# switches_place.net
KiCad netlist of a schematic drawn in Altium Designer
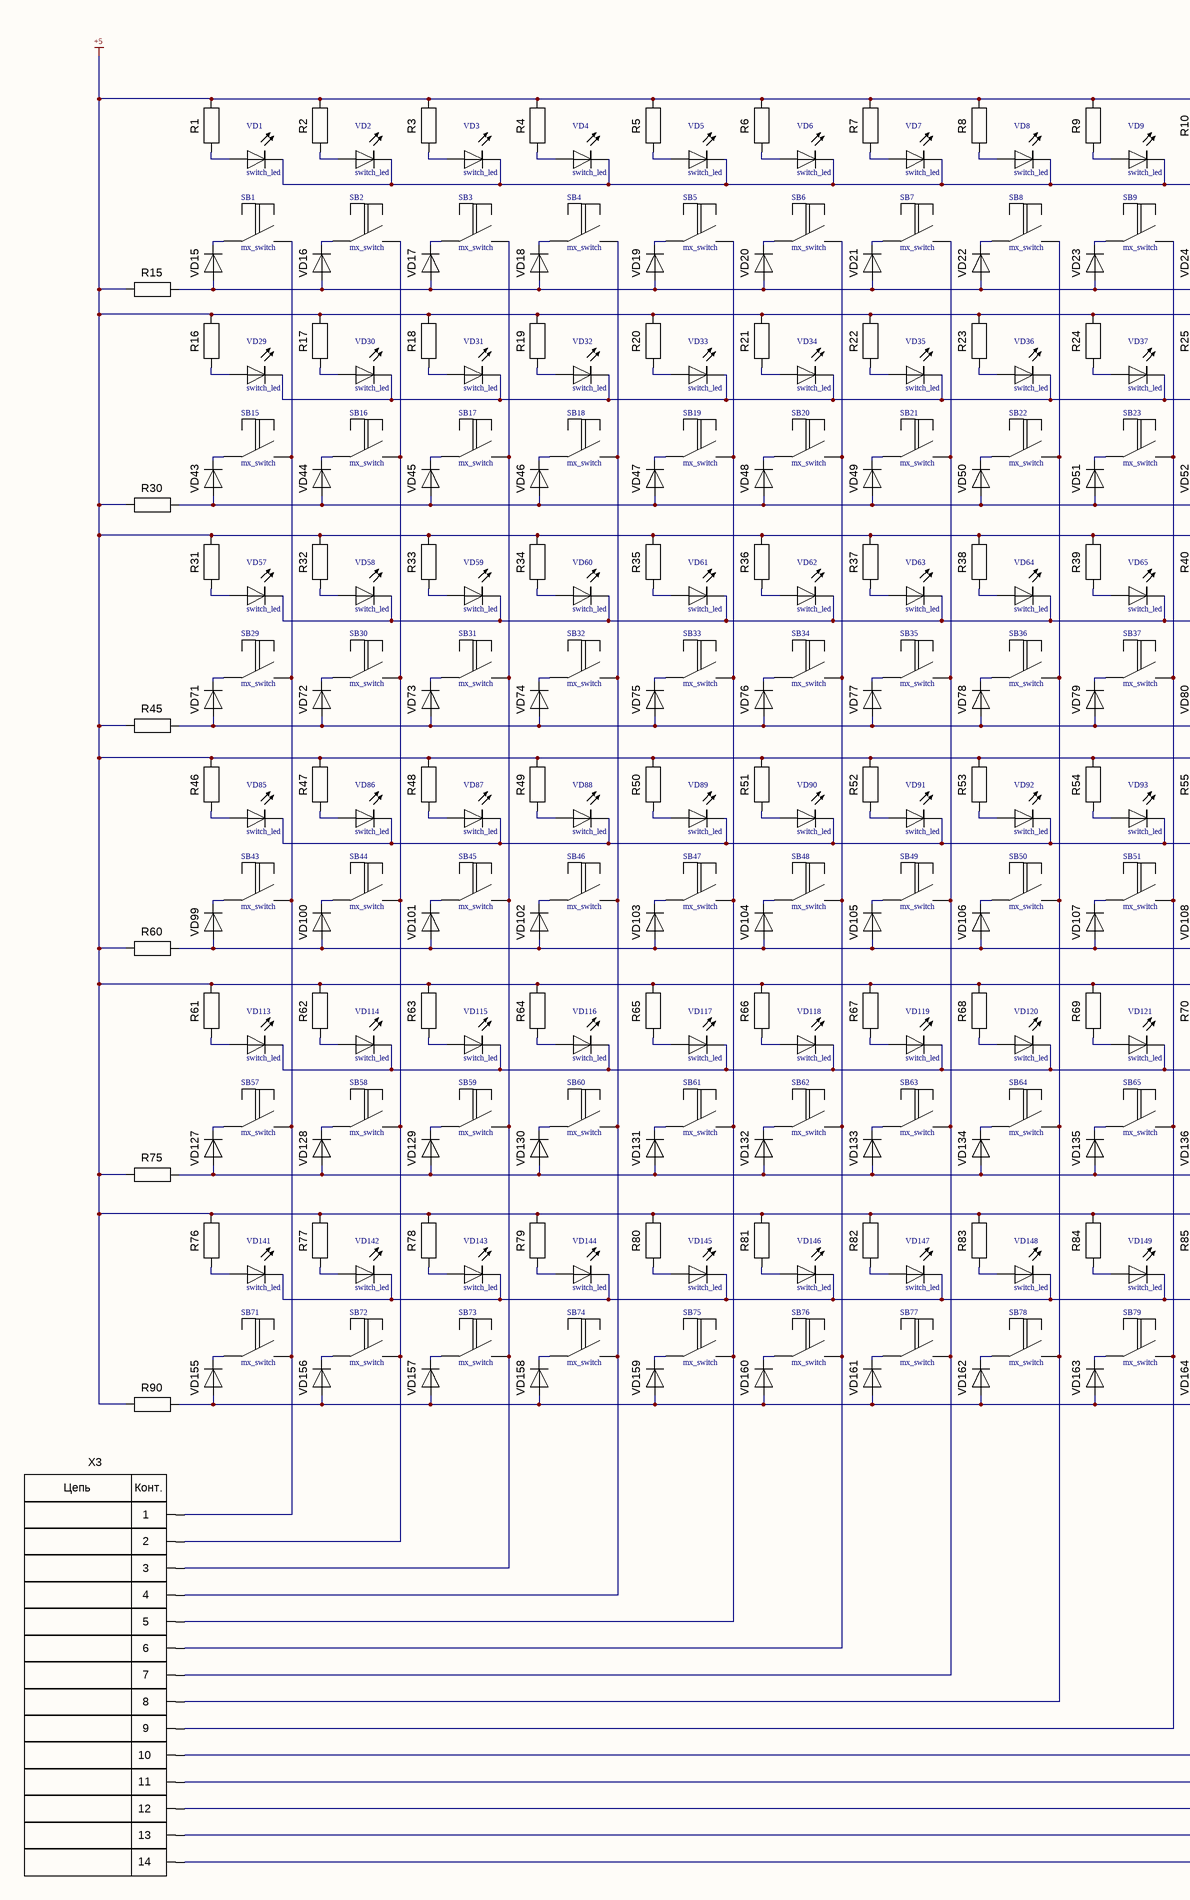
[diagram p0: switches_place.SchDoc, left]
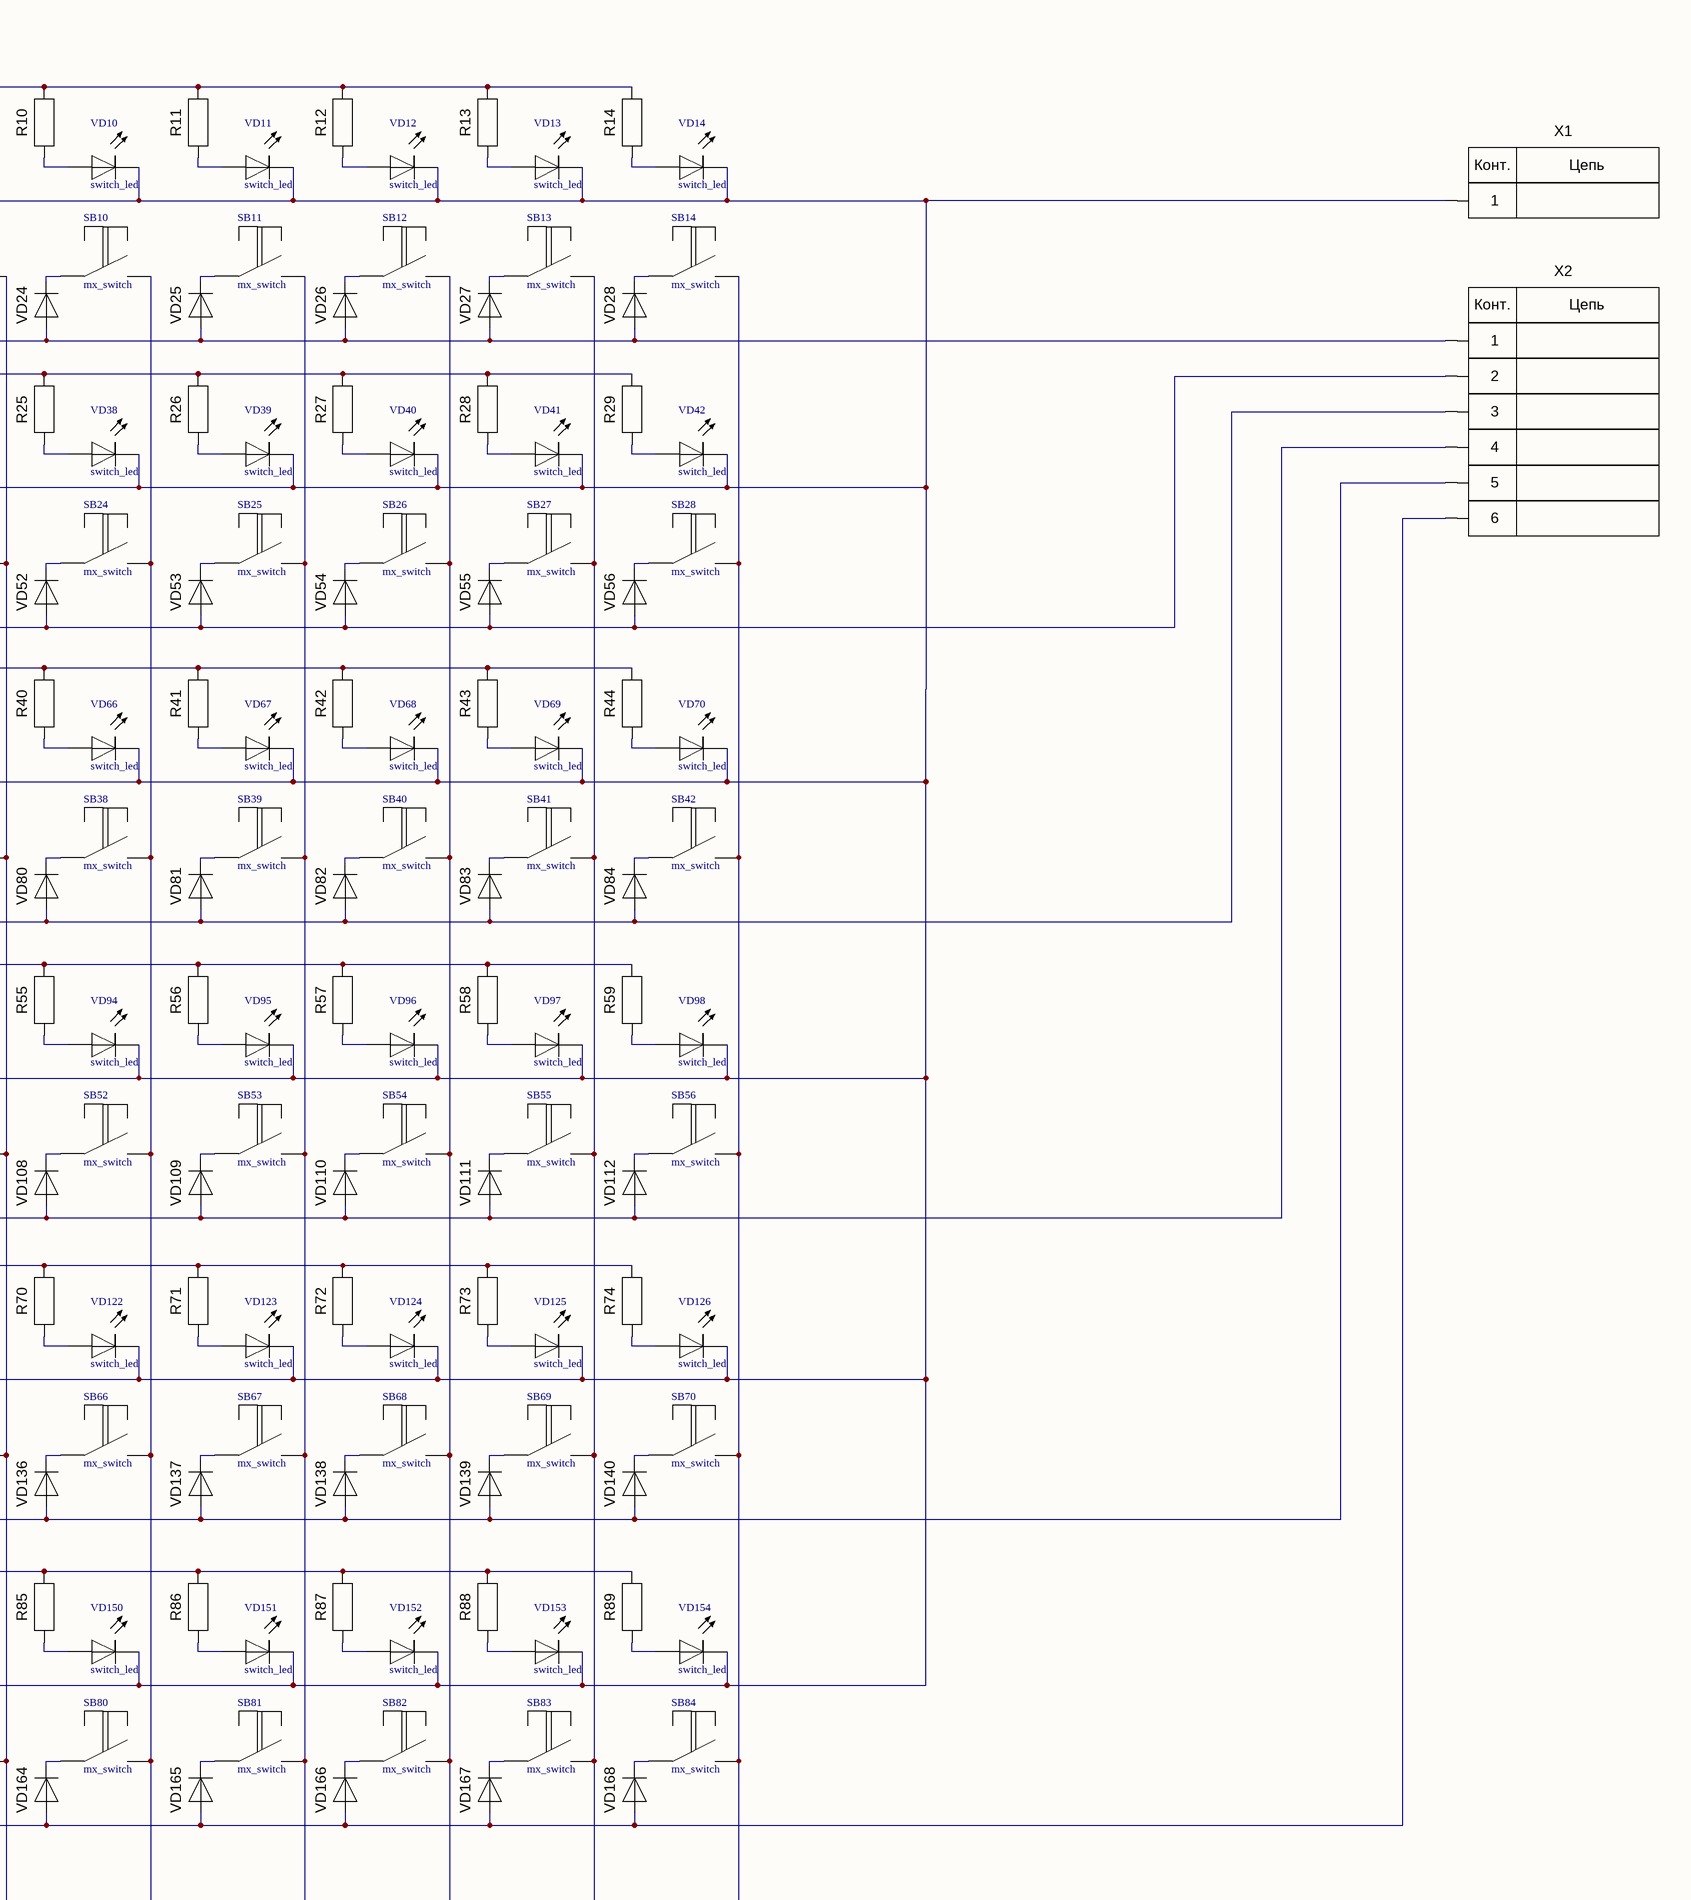
[diagram p1: switches_place.SchDoc, right]

(export (version "E")
  (design (tool "Eeschema 10.0.6"))
  (components
    (comp (ref "R1")
      (value "R")
      (footprint "R_1206")
      (fields
        (field (name "PART NUMBER") "Резистор RC1206FR-0728KL (28 кОм +-1%)")
        (field (name "TOLERANCE") "±1%")
        (field (name "POWER") "0.25 W")
      )
      (libsource (lib "GOST") (part "R"))
    )
    (comp (ref "R2")
      (value "R")
      (footprint "R_1206")
      (fields
        (field (name "PART NUMBER") "Резистор RC1206FR-0728KL (28 кОм +-1%)")
        (field (name "TOLERANCE") "±1%")
        (field (name "POWER") "0.25 W")
      )
      (libsource (lib "GOST") (part "R"))
    )
    (comp (ref "R3")
      (value "R")
      (footprint "R_1206")
      (fields
        (field (name "PART NUMBER") "Резистор RC1206FR-0728KL (28 кОм +-1%)")
        (field (name "TOLERANCE") "±1%")
        (field (name "POWER") "0.25 W")
      )
      (libsource (lib "GOST") (part "R"))
    )
    (comp (ref "R4")
      (value "R")
      (footprint "R_1206")
      (fields
        (field (name "PART NUMBER") "Резистор RC1206FR-0728KL (28 кОм +-1%)")
        (field (name "TOLERANCE") "±1%")
        (field (name "POWER") "0.25 W")
      )
      (libsource (lib "GOST") (part "R"))
    )
    (comp (ref "R5")
      (value "R")
      (footprint "R_1206")
      (fields
        (field (name "PART NUMBER") "Резистор RC1206FR-0728KL (28 кОм +-1%)")
        (field (name "TOLERANCE") "±1%")
        (field (name "POWER") "0.25 W")
      )
      (libsource (lib "GOST") (part "R"))
    )
    (comp (ref "R6")
      (value "R")
      (footprint "R_1206")
      (fields
        (field (name "PART NUMBER") "Резистор RC1206FR-0728KL (28 кОм +-1%)")
        (field (name "TOLERANCE") "±1%")
        (field (name "POWER") "0.25 W")
      )
      (libsource (lib "GOST") (part "R"))
    )
    (comp (ref "R7")
      (value "R")
      (footprint "R_1206")
      (fields
        (field (name "PART NUMBER") "Резистор RC1206FR-0728KL (28 кОм +-1%)")
        (field (name "TOLERANCE") "±1%")
        (field (name "POWER") "0.25 W")
      )
      (libsource (lib "GOST") (part "R"))
    )
    (comp (ref "R8")
      (value "R")
      (footprint "R_1206")
      (fields
        (field (name "PART NUMBER") "Резистор RC1206FR-0728KL (28 кОм +-1%)")
        (field (name "TOLERANCE") "±1%")
        (field (name "POWER") "0.25 W")
      )
      (libsource (lib "GOST") (part "R"))
    )
    (comp (ref "R9")
      (value "R")
      (footprint "R_1206")
      (fields
        (field (name "PART NUMBER") "Резистор RC1206FR-0728KL (28 кОм +-1%)")
        (field (name "TOLERANCE") "±1%")
        (field (name "POWER") "0.25 W")
      )
      (libsource (lib "GOST") (part "R"))
    )
    (comp (ref "R10")
      (value "R")
      (footprint "R_1206")
      (fields
        (field (name "PART NUMBER") "Резистор RC1206FR-0728KL (28 кОм +-1%)")
        (field (name "TOLERANCE") "±1%")
        (field (name "POWER") "0.25 W")
      )
      (libsource (lib "GOST") (part "R"))
    )
    (comp (ref "R11")
      (value "R")
      (footprint "R_1206")
      (fields
        (field (name "PART NUMBER") "Резистор RC1206FR-0728KL (28 кОм +-1%)")
        (field (name "TOLERANCE") "±1%")
        (field (name "POWER") "0.25 W")
      )
      (libsource (lib "GOST") (part "R"))
    )
    (comp (ref "R12")
      (value "R")
      (footprint "R_1206")
      (fields
        (field (name "PART NUMBER") "Резистор RC1206FR-0728KL (28 кОм +-1%)")
        (field (name "TOLERANCE") "±1%")
        (field (name "POWER") "0.25 W")
      )
      (libsource (lib "GOST") (part "R"))
    )
    (comp (ref "R13")
      (value "R")
      (footprint "R_1206")
      (fields
        (field (name "PART NUMBER") "Резистор RC1206FR-0728KL (28 кОм +-1%)")
        (field (name "TOLERANCE") "±1%")
        (field (name "POWER") "0.25 W")
      )
      (libsource (lib "GOST") (part "R"))
    )
    (comp (ref "R14")
      (value "R")
      (footprint "R_1206")
      (fields
        (field (name "PART NUMBER") "Резистор RC1206FR-0728KL (28 кОм +-1%)")
        (field (name "TOLERANCE") "±1%")
        (field (name "POWER") "0.25 W")
      )
      (libsource (lib "GOST") (part "R"))
    )
    (comp (ref "R15")
      (value "R")
      (footprint "R_1206")
      (fields
        (field (name "PART NUMBER") "Резистор RC1206FR-0716K5L (16.5 кОм +-1%)")
        (field (name "TOLERANCE") "±1%")
        (field (name "POWER") "0.25 W")
      )
      (libsource (lib "GOST") (part "R"))
    )
    (comp (ref "R16")
      (value "R")
      (footprint "R_1206")
      (fields
        (field (name "PART NUMBER") "Резистор RC1206FR-0728KL (28 кОм +-1%)")
        (field (name "TOLERANCE") "±1%")
        (field (name "POWER") "0.25 W")
      )
      (libsource (lib "GOST") (part "R"))
    )
    (comp (ref "R17")
      (value "R")
      (footprint "R_1206")
      (fields
        (field (name "PART NUMBER") "Резистор RC1206FR-0728KL (28 кОм +-1%)")
        (field (name "TOLERANCE") "±1%")
        (field (name "POWER") "0.25 W")
      )
      (libsource (lib "GOST") (part "R"))
    )
    (comp (ref "R18")
      (value "R")
      (footprint "R_1206")
      (fields
        (field (name "PART NUMBER") "Резистор RC1206FR-0728KL (28 кОм +-1%)")
        (field (name "TOLERANCE") "±1%")
        (field (name "POWER") "0.25 W")
      )
      (libsource (lib "GOST") (part "R"))
    )
    (comp (ref "R19")
      (value "R")
      (footprint "R_1206")
      (fields
        (field (name "PART NUMBER") "Резистор RC1206FR-0728KL (28 кОм +-1%)")
        (field (name "TOLERANCE") "±1%")
        (field (name "POWER") "0.25 W")
      )
      (libsource (lib "GOST") (part "R"))
    )
    (comp (ref "R20")
      (value "R")
      (footprint "R_1206")
      (fields
        (field (name "PART NUMBER") "Резистор RC1206FR-0728KL (28 кОм +-1%)")
        (field (name "TOLERANCE") "±1%")
        (field (name "POWER") "0.25 W")
      )
      (libsource (lib "GOST") (part "R"))
    )
    (comp (ref "R21")
      (value "R")
      (footprint "R_1206")
      (fields
        (field (name "PART NUMBER") "Резистор RC1206FR-0728KL (28 кОм +-1%)")
        (field (name "TOLERANCE") "±1%")
        (field (name "POWER") "0.25 W")
      )
      (libsource (lib "GOST") (part "R"))
    )
    (comp (ref "R22")
      (value "R")
      (footprint "R_1206")
      (fields
        (field (name "PART NUMBER") "Резистор RC1206FR-0728KL (28 кОм +-1%)")
        (field (name "TOLERANCE") "±1%")
        (field (name "POWER") "0.25 W")
      )
      (libsource (lib "GOST") (part "R"))
    )
    (comp (ref "R23")
      (value "R")
      (footprint "R_1206")
      (fields
        (field (name "PART NUMBER") "Резистор RC1206FR-0728KL (28 кОм +-1%)")
        (field (name "TOLERANCE") "±1%")
        (field (name "POWER") "0.25 W")
      )
      (libsource (lib "GOST") (part "R"))
    )
    (comp (ref "R24")
      (value "R")
      (footprint "R_1206")
      (fields
        (field (name "PART NUMBER") "Резистор RC1206FR-0728KL (28 кОм +-1%)")
        (field (name "TOLERANCE") "±1%")
        (field (name "POWER") "0.25 W")
      )
      (libsource (lib "GOST") (part "R"))
    )
    (comp (ref "R25")
      (value "R")
      (footprint "R_1206")
      (fields
        (field (name "PART NUMBER") "Резистор RC1206FR-0728KL (28 кОм +-1%)")
        (field (name "TOLERANCE") "±1%")
        (field (name "POWER") "0.25 W")
      )
      (libsource (lib "GOST") (part "R"))
    )
    (comp (ref "R26")
      (value "R")
      (footprint "R_1206")
      (fields
        (field (name "PART NUMBER") "Резистор RC1206FR-0728KL (28 кОм +-1%)")
        (field (name "TOLERANCE") "±1%")
        (field (name "POWER") "0.25 W")
      )
      (libsource (lib "GOST") (part "R"))
    )
    (comp (ref "R27")
      (value "R")
      (footprint "R_1206")
      (fields
        (field (name "PART NUMBER") "Резистор RC1206FR-0728KL (28 кОм +-1%)")
        (field (name "TOLERANCE") "±1%")
        (field (name "POWER") "0.25 W")
      )
      (libsource (lib "GOST") (part "R"))
    )
    (comp (ref "R28")
      (value "R")
      (footprint "R_1206")
      (fields
        (field (name "PART NUMBER") "Резистор RC1206FR-0728KL (28 кОм +-1%)")
        (field (name "TOLERANCE") "±1%")
        (field (name "POWER") "0.25 W")
      )
      (libsource (lib "GOST") (part "R"))
    )
    (comp (ref "R29")
      (value "R")
      (footprint "R_1206")
      (fields
        (field (name "PART NUMBER") "Резистор RC1206FR-0728KL (28 кОм +-1%)")
        (field (name "TOLERANCE") "±1%")
        (field (name "POWER") "0.25 W")
      )
      (libsource (lib "GOST") (part "R"))
    )
    (comp (ref "R30")
      (value "R")
      (footprint "R_1206")
      (fields
        (field (name "PART NUMBER") "Резистор RC1206FR-0716K5L (16.5 кОм +-1%)")
        (field (name "TOLERANCE") "±1%")
        (field (name "POWER") "0.25 W")
      )
      (libsource (lib "GOST") (part "R"))
    )
    (comp (ref "R31")
      (value "R")
      (footprint "R_1206")
      (fields
        (field (name "PART NUMBER") "Резистор RC1206FR-0728KL (28 кОм +-1%)")
        (field (name "TOLERANCE") "±1%")
        (field (name "POWER") "0.25 W")
      )
      (libsource (lib "GOST") (part "R"))
    )
    (comp (ref "R32")
      (value "R")
      (footprint "R_1206")
      (fields
        (field (name "PART NUMBER") "Резистор RC1206FR-0728KL (28 кОм +-1%)")
        (field (name "TOLERANCE") "±1%")
        (field (name "POWER") "0.25 W")
      )
      (libsource (lib "GOST") (part "R"))
    )
    (comp (ref "R33")
      (value "R")
      (footprint "R_1206")
      (fields
        (field (name "PART NUMBER") "Резистор RC1206FR-0728KL (28 кОм +-1%)")
        (field (name "TOLERANCE") "±1%")
        (field (name "POWER") "0.25 W")
      )
      (libsource (lib "GOST") (part "R"))
    )
    (comp (ref "R34")
      (value "R")
      (footprint "R_1206")
      (fields
        (field (name "PART NUMBER") "Резистор RC1206FR-0728KL (28 кОм +-1%)")
        (field (name "TOLERANCE") "±1%")
        (field (name "POWER") "0.25 W")
      )
      (libsource (lib "GOST") (part "R"))
    )
    (comp (ref "R35")
      (value "R")
      (footprint "R_1206")
      (fields
        (field (name "PART NUMBER") "Резистор RC1206FR-0728KL (28 кОм +-1%)")
        (field (name "TOLERANCE") "±1%")
        (field (name "POWER") "0.25 W")
      )
      (libsource (lib "GOST") (part "R"))
    )
    (comp (ref "R36")
      (value "R")
      (footprint "R_1206")
      (fields
        (field (name "PART NUMBER") "Резистор RC1206FR-0728KL (28 кОм +-1%)")
        (field (name "TOLERANCE") "±1%")
        (field (name "POWER") "0.25 W")
      )
      (libsource (lib "GOST") (part "R"))
    )
    (comp (ref "R37")
      (value "R")
      (footprint "R_1206")
      (fields
        (field (name "PART NUMBER") "Резистор RC1206FR-0728KL (28 кОм +-1%)")
        (field (name "TOLERANCE") "±1%")
        (field (name "POWER") "0.25 W")
      )
      (libsource (lib "GOST") (part "R"))
    )
    (comp (ref "R38")
      (value "R")
      (footprint "R_1206")
      (fields
        (field (name "PART NUMBER") "Резистор RC1206FR-0728KL (28 кОм +-1%)")
        (field (name "TOLERANCE") "±1%")
        (field (name "POWER") "0.25 W")
      )
      (libsource (lib "GOST") (part "R"))
    )
    (comp (ref "R39")
      (value "R")
      (footprint "R_1206")
      (fields
        (field (name "PART NUMBER") "Резистор RC1206FR-0728KL (28 кОм +-1%)")
        (field (name "TOLERANCE") "±1%")
        (field (name "POWER") "0.25 W")
      )
      (libsource (lib "GOST") (part "R"))
    )
    (comp (ref "R40")
      (value "R")
      (footprint "R_1206")
      (fields
        (field (name "PART NUMBER") "Резистор RC1206FR-0728KL (28 кОм +-1%)")
        (field (name "TOLERANCE") "±1%")
        (field (name "POWER") "0.25 W")
      )
      (libsource (lib "GOST") (part "R"))
    )
    (comp (ref "R41")
      (value "R")
      (footprint "R_1206")
      (fields
        (field (name "PART NUMBER") "Резистор RC1206FR-0728KL (28 кОм +-1%)")
        (field (name "TOLERANCE") "±1%")
        (field (name "POWER") "0.25 W")
      )
      (libsource (lib "GOST") (part "R"))
    )
    (comp (ref "R42")
      (value "R")
      (footprint "R_1206")
      (fields
        (field (name "PART NUMBER") "Резистор RC1206FR-0728KL (28 кОм +-1%)")
        (field (name "TOLERANCE") "±1%")
        (field (name "POWER") "0.25 W")
      )
      (libsource (lib "GOST") (part "R"))
    )
    (comp (ref "R43")
      (value "R")
      (footprint "R_1206")
      (fields
        (field (name "PART NUMBER") "Резистор RC1206FR-0728KL (28 кОм +-1%)")
        (field (name "TOLERANCE") "±1%")
        (field (name "POWER") "0.25 W")
      )
      (libsource (lib "GOST") (part "R"))
    )
    (comp (ref "R44")
      (value "R")
      (footprint "R_1206")
      (fields
        (field (name "PART NUMBER") "Резистор RC1206FR-0728KL (28 кОм +-1%)")
        (field (name "TOLERANCE") "±1%")
        (field (name "POWER") "0.25 W")
      )
      (libsource (lib "GOST") (part "R"))
    )
    (comp (ref "R45")
      (value "R")
      (footprint "R_1206")
      (fields
        (field (name "PART NUMBER") "Резистор RC1206FR-0716K5L (16.5 кОм +-1%)")
        (field (name "TOLERANCE") "±1%")
        (field (name "POWER") "0.25 W")
      )
      (libsource (lib "GOST") (part "R"))
    )
    (comp (ref "R46")
      (value "R")
      (footprint "R_1206")
      (fields
        (field (name "PART NUMBER") "Резистор RC1206FR-0728KL (28 кОм +-1%)")
        (field (name "TOLERANCE") "±1%")
        (field (name "POWER") "0.25 W")
      )
      (libsource (lib "GOST") (part "R"))
    )
    (comp (ref "R47")
      (value "R")
      (footprint "R_1206")
      (fields
        (field (name "PART NUMBER") "Резистор RC1206FR-0728KL (28 кОм +-1%)")
        (field (name "TOLERANCE") "±1%")
        (field (name "POWER") "0.25 W")
      )
      (libsource (lib "GOST") (part "R"))
    )
    (comp (ref "R48")
      (value "R")
      (footprint "R_1206")
      (fields
        (field (name "PART NUMBER") "Резистор RC1206FR-0728KL (28 кОм +-1%)")
        (field (name "TOLERANCE") "±1%")
        (field (name "POWER") "0.25 W")
      )
      (libsource (lib "GOST") (part "R"))
    )
    (comp (ref "R49")
      (value "R")
      (footprint "R_1206")
      (fields
        (field (name "PART NUMBER") "Резистор RC1206FR-0728KL (28 кОм +-1%)")
        (field (name "TOLERANCE") "±1%")
        (field (name "POWER") "0.25 W")
      )
      (libsource (lib "GOST") (part "R"))
    )
    (comp (ref "R50")
      (value "R")
      (footprint "R_1206")
      (fields
        (field (name "PART NUMBER") "Резистор RC1206FR-0728KL (28 кОм +-1%)")
        (field (name "TOLERANCE") "±1%")
        (field (name "POWER") "0.25 W")
      )
      (libsource (lib "GOST") (part "R"))
    )
    (comp (ref "R51")
      (value "R")
      (footprint "R_1206")
      (fields
        (field (name "PART NUMBER") "Резистор RC1206FR-0728KL (28 кОм +-1%)")
        (field (name "TOLERANCE") "±1%")
        (field (name "POWER") "0.25 W")
      )
      (libsource (lib "GOST") (part "R"))
    )
    (comp (ref "R52")
      (value "R")
      (footprint "R_1206")
      (fields
        (field (name "PART NUMBER") "Резистор RC1206FR-0728KL (28 кОм +-1%)")
        (field (name "TOLERANCE") "±1%")
        (field (name "POWER") "0.25 W")
      )
      (libsource (lib "GOST") (part "R"))
    )
    (comp (ref "R53")
      (value "R")
      (footprint "R_1206")
      (fields
        (field (name "PART NUMBER") "Резистор RC1206FR-0728KL (28 кОм +-1%)")
        (field (name "TOLERANCE") "±1%")
        (field (name "POWER") "0.25 W")
      )
      (libsource (lib "GOST") (part "R"))
    )
    (comp (ref "R54")
      (value "R")
      (footprint "R_1206")
      (fields
        (field (name "PART NUMBER") "Резистор RC1206FR-0728KL (28 кОм +-1%)")
        (field (name "TOLERANCE") "±1%")
        (field (name "POWER") "0.25 W")
      )
      (libsource (lib "GOST") (part "R"))
    )
    (comp (ref "R55")
      (value "R")
      (footprint "R_1206")
      (fields
        (field (name "PART NUMBER") "Резистор RC1206FR-0728KL (28 кОм +-1%)")
        (field (name "TOLERANCE") "±1%")
        (field (name "POWER") "0.25 W")
      )
      (libsource (lib "GOST") (part "R"))
    )
    (comp (ref "R56")
      (value "R")
      (footprint "R_1206")
      (fields
        (field (name "PART NUMBER") "Резистор RC1206FR-0728KL (28 кОм +-1%)")
        (field (name "TOLERANCE") "±1%")
        (field (name "POWER") "0.25 W")
      )
      (libsource (lib "GOST") (part "R"))
    )
    (comp (ref "R57")
      (value "R")
      (footprint "R_1206")
      (fields
        (field (name "PART NUMBER") "Резистор RC1206FR-0728KL (28 кОм +-1%)")
        (field (name "TOLERANCE") "±1%")
        (field (name "POWER") "0.25 W")
      )
      (libsource (lib "GOST") (part "R"))
    )
    (comp (ref "R58")
      (value "R")
      (footprint "R_1206")
      (fields
        (field (name "PART NUMBER") "Резистор RC1206FR-0728KL (28 кОм +-1%)")
        (field (name "TOLERANCE") "±1%")
        (field (name "POWER") "0.25 W")
      )
      (libsource (lib "GOST") (part "R"))
    )
    (comp (ref "R59")
      (value "R")
      (footprint "R_1206")
      (fields
        (field (name "PART NUMBER") "Резистор RC1206FR-0728KL (28 кОм +-1%)")
        (field (name "TOLERANCE") "±1%")
        (field (name "POWER") "0.25 W")
      )
      (libsource (lib "GOST") (part "R"))
    )
    (comp (ref "R60")
      (value "R")
      (footprint "R_1206")
      (fields
        (field (name "PART NUMBER") "Резистор RC1206FR-0716K5L (16.5 кОм +-1%)")
        (field (name "TOLERANCE") "±1%")
        (field (name "POWER") "0.25 W")
      )
      (libsource (lib "GOST") (part "R"))
    )
    (comp (ref "R61")
      (value "R")
      (footprint "R_1206")
      (fields
        (field (name "PART NUMBER") "Резистор RC1206FR-0728KL (28 кОм +-1%)")
        (field (name "TOLERANCE") "±1%")
        (field (name "POWER") "0.25 W")
      )
      (libsource (lib "GOST") (part "R"))
    )
    (comp (ref "R62")
      (value "R")
      (footprint "R_1206")
      (fields
        (field (name "PART NUMBER") "Резистор RC1206FR-0728KL (28 кОм +-1%)")
        (field (name "TOLERANCE") "±1%")
        (field (name "POWER") "0.25 W")
      )
      (libsource (lib "GOST") (part "R"))
    )
    (comp (ref "R63")
      (value "R")
      (footprint "R_1206")
      (fields
        (field (name "PART NUMBER") "Резистор RC1206FR-0728KL (28 кОм +-1%)")
        (field (name "TOLERANCE") "±1%")
        (field (name "POWER") "0.25 W")
      )
      (libsource (lib "GOST") (part "R"))
    )
    (comp (ref "R64")
      (value "R")
      (footprint "R_1206")
      (fields
        (field (name "PART NUMBER") "Резистор RC1206FR-0728KL (28 кОм +-1%)")
        (field (name "TOLERANCE") "±1%")
        (field (name "POWER") "0.25 W")
      )
      (libsource (lib "GOST") (part "R"))
    )
    (comp (ref "R65")
      (value "R")
      (footprint "R_1206")
      (fields
        (field (name "PART NUMBER") "Резистор RC1206FR-0728KL (28 кОм +-1%)")
        (field (name "TOLERANCE") "±1%")
        (field (name "POWER") "0.25 W")
      )
      (libsource (lib "GOST") (part "R"))
    )
    (comp (ref "R66")
      (value "R")
      (footprint "R_1206")
      (fields
        (field (name "PART NUMBER") "Резистор RC1206FR-0728KL (28 кОм +-1%)")
        (field (name "TOLERANCE") "±1%")
        (field (name "POWER") "0.25 W")
      )
      (libsource (lib "GOST") (part "R"))
    )
    (comp (ref "R67")
      (value "R")
      (footprint "R_1206")
      (fields
        (field (name "PART NUMBER") "Резистор RC1206FR-0728KL (28 кОм +-1%)")
        (field (name "TOLERANCE") "±1%")
        (field (name "POWER") "0.25 W")
      )
      (libsource (lib "GOST") (part "R"))
    )
    (comp (ref "R68")
      (value "R")
      (footprint "R_1206")
      (fields
        (field (name "PART NUMBER") "Резистор RC1206FR-0728KL (28 кОм +-1%)")
        (field (name "TOLERANCE") "±1%")
        (field (name "POWER") "0.25 W")
      )
      (libsource (lib "GOST") (part "R"))
    )
    (comp (ref "R69")
      (value "R")
      (footprint "R_1206")
      (fields
        (field (name "PART NUMBER") "Резистор RC1206FR-0728KL (28 кОм +-1%)")
        (field (name "TOLERANCE") "±1%")
        (field (name "POWER") "0.25 W")
      )
      (libsource (lib "GOST") (part "R"))
    )
    (comp (ref "R70")
      (value "R")
      (footprint "R_1206")
      (fields
        (field (name "PART NUMBER") "Резистор RC1206FR-0728KL (28 кОм +-1%)")
        (field (name "TOLERANCE") "±1%")
        (field (name "POWER") "0.25 W")
      )
      (libsource (lib "GOST") (part "R"))
    )
    (comp (ref "R71")
      (value "R")
      (footprint "R_1206")
      (fields
        (field (name "PART NUMBER") "Резистор RC1206FR-0728KL (28 кОм +-1%)")
        (field (name "TOLERANCE") "±1%")
        (field (name "POWER") "0.25 W")
      )
      (libsource (lib "GOST") (part "R"))
    )
    (comp (ref "R72")
      (value "R")
      (footprint "R_1206")
      (fields
        (field (name "PART NUMBER") "Резистор RC1206FR-0728KL (28 кОм +-1%)")
        (field (name "TOLERANCE") "±1%")
        (field (name "POWER") "0.25 W")
      )
      (libsource (lib "GOST") (part "R"))
    )
    (comp (ref "R73")
      (value "R")
      (footprint "R_1206")
      (fields
        (field (name "PART NUMBER") "Резистор RC1206FR-0728KL (28 кОм +-1%)")
        (field (name "TOLERANCE") "±1%")
        (field (name "POWER") "0.25 W")
      )
      (libsource (lib "GOST") (part "R"))
    )
    (comp (ref "R74")
      (value "R")
      (footprint "R_1206")
      (fields
        (field (name "PART NUMBER") "Резистор RC1206FR-0728KL (28 кОм +-1%)")
        (field (name "TOLERANCE") "±1%")
        (field (name "POWER") "0.25 W")
      )
      (libsource (lib "GOST") (part "R"))
    )
    (comp (ref "R75")
      (value "R")
      (footprint "R_1206")
      (fields
        (field (name "PART NUMBER") "Резистор RC1206FR-0716K5L (16.5 кОм +-1%)")
        (field (name "TOLERANCE") "±1%")
        (field (name "POWER") "0.25 W")
      )
      (libsource (lib "GOST") (part "R"))
    )
    (comp (ref "R76")
      (value "R")
      (footprint "R_1206")
      (fields
        (field (name "PART NUMBER") "Резистор RC1206FR-0728KL (28 кОм +-1%)")
        (field (name "TOLERANCE") "±1%")
        (field (name "POWER") "0.25 W")
      )
      (libsource (lib "GOST") (part "R"))
    )
    (comp (ref "R77")
      (value "R")
      (footprint "R_1206")
      (fields
        (field (name "PART NUMBER") "Резистор RC1206FR-0728KL (28 кОм +-1%)")
        (field (name "TOLERANCE") "±1%")
        (field (name "POWER") "0.25 W")
      )
      (libsource (lib "GOST") (part "R"))
    )
    (comp (ref "R78")
      (value "R")
      (footprint "R_1206")
      (fields
        (field (name "PART NUMBER") "Резистор RC1206FR-0728KL (28 кОм +-1%)")
        (field (name "TOLERANCE") "±1%")
        (field (name "POWER") "0.25 W")
      )
      (libsource (lib "GOST") (part "R"))
    )
    (comp (ref "R79")
      (value "R")
      (footprint "R_1206")
      (fields
        (field (name "PART NUMBER") "Резистор RC1206FR-0728KL (28 кОм +-1%)")
        (field (name "TOLERANCE") "±1%")
        (field (name "POWER") "0.25 W")
      )
      (libsource (lib "GOST") (part "R"))
    )
    (comp (ref "R80")
      (value "R")
      (footprint "R_1206")
      (fields
        (field (name "PART NUMBER") "Резистор RC1206FR-0728KL (28 кОм +-1%)")
        (field (name "TOLERANCE") "±1%")
        (field (name "POWER") "0.25 W")
      )
      (libsource (lib "GOST") (part "R"))
    )
    (comp (ref "R81")
      (value "R")
      (footprint "R_1206")
      (fields
        (field (name "PART NUMBER") "Резистор RC1206FR-0728KL (28 кОм +-1%)")
        (field (name "TOLERANCE") "±1%")
        (field (name "POWER") "0.25 W")
      )
      (libsource (lib "GOST") (part "R"))
    )
    (comp (ref "R82")
      (value "R")
      (footprint "R_1206")
      (fields
        (field (name "PART NUMBER") "Резистор RC1206FR-0728KL (28 кОм +-1%)")
        (field (name "TOLERANCE") "±1%")
        (field (name "POWER") "0.25 W")
      )
      (libsource (lib "GOST") (part "R"))
    )
    (comp (ref "R83")
      (value "R")
      (footprint "R_1206")
      (fields
        (field (name "PART NUMBER") "Резистор RC1206FR-0728KL (28 кОм +-1%)")
        (field (name "TOLERANCE") "±1%")
        (field (name "POWER") "0.25 W")
      )
      (libsource (lib "GOST") (part "R"))
    )
    (comp (ref "R84")
      (value "R")
      (footprint "R_1206")
      (fields
        (field (name "PART NUMBER") "Резистор RC1206FR-0728KL (28 кОм +-1%)")
        (field (name "TOLERANCE") "±1%")
        (field (name "POWER") "0.25 W")
      )
      (libsource (lib "GOST") (part "R"))
    )
    (comp (ref "R85")
      (value "R")
      (footprint "R_1206")
      (fields
        (field (name "PART NUMBER") "Резистор RC1206FR-0728KL (28 кОм +-1%)")
        (field (name "TOLERANCE") "±1%")
        (field (name "POWER") "0.25 W")
      )
      (libsource (lib "GOST") (part "R"))
    )
    (comp (ref "R86")
      (value "R")
      (footprint "R_1206")
      (fields
        (field (name "PART NUMBER") "Резистор RC1206FR-0728KL (28 кОм +-1%)")
        (field (name "TOLERANCE") "±1%")
        (field (name "POWER") "0.25 W")
      )
      (libsource (lib "GOST") (part "R"))
    )
    (comp (ref "R87")
      (value "R")
      (footprint "R_1206")
      (fields
        (field (name "PART NUMBER") "Резистор RC1206FR-0728KL (28 кОм +-1%)")
        (field (name "TOLERANCE") "±1%")
        (field (name "POWER") "0.25 W")
      )
      (libsource (lib "GOST") (part "R"))
    )
    (comp (ref "R88")
      (value "R")
      (footprint "R_1206")
      (fields
        (field (name "PART NUMBER") "Резистор RC1206FR-0728KL (28 кОм +-1%)")
        (field (name "TOLERANCE") "±1%")
        (field (name "POWER") "0.25 W")
      )
      (libsource (lib "GOST") (part "R"))
    )
    (comp (ref "R89")
      (value "R")
      (footprint "R_1206")
      (fields
        (field (name "PART NUMBER") "Резистор RC1206FR-0728KL (28 кОм +-1%)")
        (field (name "TOLERANCE") "±1%")
        (field (name "POWER") "0.25 W")
      )
      (libsource (lib "GOST") (part "R"))
    )
    (comp (ref "R90")
      (value "R")
      (footprint "R_1206")
      (fields
        (field (name "PART NUMBER") "Резистор RC1206FR-0716K5L (16.5 кОм +-1%)")
        (field (name "TOLERANCE") "±1%")
        (field (name "POWER") "0.25 W")
      )
      (libsource (lib "GOST") (part "R"))
    )
    (comp (ref "SB1")
      (value "mx_switch")
      (footprint "cherry_mx_5pin_led")
      (libsource (lib "cherry_mx_switch") (part "mx_switch"))
    )
    (comp (ref "SB2")
      (value "mx_switch")
      (footprint "cherry_mx_5pin_led")
      (libsource (lib "cherry_mx_switch") (part "mx_switch"))
    )
    (comp (ref "SB3")
      (value "mx_switch")
      (footprint "cherry_mx_5pin_led")
      (libsource (lib "cherry_mx_switch") (part "mx_switch"))
    )
    (comp (ref "SB4")
      (value "mx_switch")
      (footprint "cherry_mx_5pin_led")
      (libsource (lib "cherry_mx_switch") (part "mx_switch"))
    )
    (comp (ref "SB5")
      (value "mx_switch")
      (footprint "cherry_mx_5pin_led")
      (libsource (lib "") (part "mx_switch_1"))
    )
    (comp (ref "SB6")
      (value "mx_switch")
      (footprint "cherry_mx_5pin_led")
      (libsource (lib "cherry_mx_switch") (part "mx_switch"))
    )
    (comp (ref "SB7")
      (value "mx_switch")
      (footprint "cherry_mx_5pin_led")
      (libsource (lib "cherry_mx_switch") (part "mx_switch"))
    )
    (comp (ref "SB8")
      (value "mx_switch")
      (footprint "cherry_mx_5pin_led")
      (libsource (lib "cherry_mx_switch") (part "mx_switch"))
    )
    (comp (ref "SB9")
      (value "mx_switch")
      (footprint "cherry_mx_5pin_led")
      (libsource (lib "cherry_mx_switch") (part "mx_switch"))
    )
    (comp (ref "SB10")
      (value "mx_switch")
      (footprint "cherry_mx_5pin_led")
      (libsource (lib "cherry_mx_switch") (part "mx_switch"))
    )
    (comp (ref "SB11")
      (value "mx_switch")
      (footprint "cherry_mx_5pin_led")
      (libsource (lib "cherry_mx_switch") (part "mx_switch"))
    )
    (comp (ref "SB12")
      (value "mx_switch")
      (footprint "cherry_mx_5pin_led")
      (libsource (lib "cherry_mx_switch") (part "mx_switch"))
    )
    (comp (ref "SB13")
      (value "mx_switch")
      (footprint "cherry_mx_5pin_led")
      (libsource (lib "cherry_mx_switch") (part "mx_switch"))
    )
    (comp (ref "SB14")
      (value "mx_switch")
      (footprint "cherry_mx_5pin_led")
      (libsource (lib "cherry_mx_switch") (part "mx_switch"))
    )
    (comp (ref "SB15")
      (value "mx_switch")
      (footprint "cherry_mx_5pin_led")
      (libsource (lib "cherry_mx_switch") (part "mx_switch"))
    )
    (comp (ref "SB16")
      (value "mx_switch")
      (footprint "cherry_mx_5pin_led")
      (libsource (lib "cherry_mx_switch") (part "mx_switch"))
    )
    (comp (ref "SB17")
      (value "mx_switch")
      (footprint "cherry_mx_5pin_led")
      (libsource (lib "cherry_mx_switch") (part "mx_switch"))
    )
    (comp (ref "SB18")
      (value "mx_switch")
      (footprint "cherry_mx_5pin_led")
      (libsource (lib "cherry_mx_switch") (part "mx_switch"))
    )
    (comp (ref "SB19")
      (value "mx_switch")
      (footprint "cherry_mx_5pin_led")
      (libsource (lib "") (part "mx_switch_1"))
    )
    (comp (ref "SB20")
      (value "mx_switch")
      (footprint "cherry_mx_5pin_led")
      (libsource (lib "cherry_mx_switch") (part "mx_switch"))
    )
    (comp (ref "SB21")
      (value "mx_switch")
      (footprint "cherry_mx_5pin_led")
      (libsource (lib "cherry_mx_switch") (part "mx_switch"))
    )
    (comp (ref "SB22")
      (value "mx_switch")
      (footprint "cherry_mx_5pin_led")
      (libsource (lib "cherry_mx_switch") (part "mx_switch"))
    )
    (comp (ref "SB23")
      (value "mx_switch")
      (footprint "cherry_mx_5pin_led")
      (libsource (lib "cherry_mx_switch") (part "mx_switch"))
    )
    (comp (ref "SB24")
      (value "mx_switch")
      (footprint "cherry_mx_5pin_led")
      (libsource (lib "cherry_mx_switch") (part "mx_switch"))
    )
    (comp (ref "SB25")
      (value "mx_switch")
      (footprint "cherry_mx_5pin_led")
      (libsource (lib "cherry_mx_switch") (part "mx_switch"))
    )
    (comp (ref "SB26")
      (value "mx_switch")
      (footprint "cherry_mx_5pin_led")
      (libsource (lib "cherry_mx_switch") (part "mx_switch"))
    )
    (comp (ref "SB27")
      (value "mx_switch")
      (footprint "cherry_mx_5pin_led")
      (libsource (lib "cherry_mx_switch") (part "mx_switch"))
    )
    (comp (ref "SB28")
      (value "mx_switch")
      (footprint "cherry_mx_5pin_led")
      (libsource (lib "cherry_mx_switch") (part "mx_switch"))
    )
    (comp (ref "SB29")
      (value "mx_switch")
      (footprint "cherry_mx_5pin_led")
      (libsource (lib "cherry_mx_switch") (part "mx_switch"))
    )
    (comp (ref "SB30")
      (value "mx_switch")
      (footprint "cherry_mx_5pin_led")
      (libsource (lib "cherry_mx_switch") (part "mx_switch"))
    )
    (comp (ref "SB31")
      (value "mx_switch")
      (footprint "cherry_mx_5pin_led")
      (libsource (lib "cherry_mx_switch") (part "mx_switch"))
    )
    (comp (ref "SB32")
      (value "mx_switch")
      (footprint "cherry_mx_5pin_led")
      (libsource (lib "cherry_mx_switch") (part "mx_switch"))
    )
    (comp (ref "SB33")
      (value "mx_switch")
      (footprint "cherry_mx_5pin_led")
      (libsource (lib "") (part "mx_switch_1"))
    )
    (comp (ref "SB34")
      (value "mx_switch")
      (footprint "cherry_mx_5pin_led")
      (libsource (lib "cherry_mx_switch") (part "mx_switch"))
    )
    (comp (ref "SB35")
      (value "mx_switch")
      (footprint "cherry_mx_5pin_led")
      (libsource (lib "cherry_mx_switch") (part "mx_switch"))
    )
    (comp (ref "SB36")
      (value "mx_switch")
      (footprint "cherry_mx_5pin_led")
      (libsource (lib "cherry_mx_switch") (part "mx_switch"))
    )
    (comp (ref "SB37")
      (value "mx_switch")
      (footprint "cherry_mx_5pin_led")
      (libsource (lib "cherry_mx_switch") (part "mx_switch"))
    )
    (comp (ref "SB38")
      (value "mx_switch")
      (footprint "cherry_mx_5pin_led")
      (libsource (lib "cherry_mx_switch") (part "mx_switch"))
    )
    (comp (ref "SB39")
      (value "mx_switch")
      (footprint "cherry_mx_5pin_led")
      (libsource (lib "cherry_mx_switch") (part "mx_switch"))
    )
    (comp (ref "SB40")
      (value "mx_switch")
      (footprint "cherry_mx_5pin_led")
      (libsource (lib "cherry_mx_switch") (part "mx_switch"))
    )
    (comp (ref "SB41")
      (value "mx_switch")
      (footprint "cherry_mx_5pin_led")
      (libsource (lib "cherry_mx_switch") (part "mx_switch"))
    )
    (comp (ref "SB42")
      (value "mx_switch")
      (footprint "cherry_mx_5pin_led")
      (libsource (lib "cherry_mx_switch") (part "mx_switch"))
    )
    (comp (ref "SB43")
      (value "mx_switch")
      (footprint "cherry_mx_5pin_led")
      (libsource (lib "cherry_mx_switch") (part "mx_switch"))
    )
    (comp (ref "SB44")
      (value "mx_switch")
      (footprint "cherry_mx_5pin_led")
      (libsource (lib "cherry_mx_switch") (part "mx_switch"))
    )
    (comp (ref "SB45")
      (value "mx_switch")
      (footprint "cherry_mx_5pin_led")
      (libsource (lib "cherry_mx_switch") (part "mx_switch"))
    )
    (comp (ref "SB46")
      (value "mx_switch")
      (footprint "cherry_mx_5pin_led")
      (libsource (lib "cherry_mx_switch") (part "mx_switch"))
    )
    (comp (ref "SB47")
      (value "mx_switch")
      (footprint "cherry_mx_5pin_led")
      (libsource (lib "") (part "mx_switch_1"))
    )
    (comp (ref "SB48")
      (value "mx_switch")
      (footprint "cherry_mx_5pin_led")
      (libsource (lib "cherry_mx_switch") (part "mx_switch"))
    )
    (comp (ref "SB49")
      (value "mx_switch")
      (footprint "cherry_mx_5pin_led")
      (libsource (lib "cherry_mx_switch") (part "mx_switch"))
    )
    (comp (ref "SB50")
      (value "mx_switch")
      (footprint "cherry_mx_5pin_led")
      (libsource (lib "cherry_mx_switch") (part "mx_switch"))
    )
    (comp (ref "SB51")
      (value "mx_switch")
      (footprint "cherry_mx_5pin_led")
      (libsource (lib "cherry_mx_switch") (part "mx_switch"))
    )
    (comp (ref "SB52")
      (value "mx_switch")
      (footprint "cherry_mx_5pin_led")
      (libsource (lib "cherry_mx_switch") (part "mx_switch"))
    )
    (comp (ref "SB53")
      (value "mx_switch")
      (footprint "cherry_mx_5pin_led")
      (libsource (lib "cherry_mx_switch") (part "mx_switch"))
    )
    (comp (ref "SB54")
      (value "mx_switch")
      (footprint "cherry_mx_5pin_led")
      (libsource (lib "cherry_mx_switch") (part "mx_switch"))
    )
    (comp (ref "SB55")
      (value "mx_switch")
      (footprint "cherry_mx_5pin_led")
      (libsource (lib "cherry_mx_switch") (part "mx_switch"))
    )
    (comp (ref "SB56")
      (value "mx_switch")
      (footprint "cherry_mx_5pin_led")
      (libsource (lib "cherry_mx_switch") (part "mx_switch"))
    )
    (comp (ref "SB57")
      (value "mx_switch")
      (footprint "cherry_mx_5pin_led")
      (libsource (lib "") (part "mx_switch_2"))
    )
    (comp (ref "SB58")
      (value "mx_switch")
      (footprint "cherry_mx_5pin_led")
      (libsource (lib "") (part "mx_switch_2"))
    )
    (comp (ref "SB59")
      (value "mx_switch")
      (footprint "cherry_mx_5pin_led")
      (libsource (lib "") (part "mx_switch_2"))
    )
    (comp (ref "SB60")
      (value "mx_switch")
      (footprint "cherry_mx_5pin_led")
      (libsource (lib "") (part "mx_switch_2"))
    )
    (comp (ref "SB61")
      (value "mx_switch")
      (footprint "cherry_mx_5pin_led")
      (libsource (lib "") (part "mx_switch_3"))
    )
    (comp (ref "SB62")
      (value "mx_switch")
      (footprint "cherry_mx_5pin_led")
      (libsource (lib "") (part "mx_switch_2"))
    )
    (comp (ref "SB63")
      (value "mx_switch")
      (footprint "cherry_mx_5pin_led")
      (libsource (lib "") (part "mx_switch_2"))
    )
    (comp (ref "SB64")
      (value "mx_switch")
      (footprint "cherry_mx_5pin_led")
      (libsource (lib "") (part "mx_switch_2"))
    )
    (comp (ref "SB65")
      (value "mx_switch")
      (footprint "cherry_mx_5pin_led")
      (libsource (lib "") (part "mx_switch_2"))
    )
    (comp (ref "SB66")
      (value "mx_switch")
      (footprint "cherry_mx_5pin_led")
      (libsource (lib "") (part "mx_switch_2"))
    )
    (comp (ref "SB67")
      (value "mx_switch")
      (footprint "cherry_mx_5pin_led")
      (libsource (lib "") (part "mx_switch_2"))
    )
    (comp (ref "SB68")
      (value "mx_switch")
      (footprint "cherry_mx_5pin_led")
      (libsource (lib "") (part "mx_switch_2"))
    )
    (comp (ref "SB69")
      (value "mx_switch")
      (footprint "cherry_mx_5pin_led")
      (libsource (lib "") (part "mx_switch_2"))
    )
    (comp (ref "SB70")
      (value "mx_switch")
      (footprint "cherry_mx_5pin_led")
      (libsource (lib "") (part "mx_switch_2"))
    )
    (comp (ref "SB71")
      (value "mx_switch")
      (footprint "cherry_mx_5pin_led")
      (libsource (lib "cherry_mx_switch") (part "mx_switch"))
    )
    (comp (ref "SB72")
      (value "mx_switch")
      (footprint "cherry_mx_5pin_led")
      (libsource (lib "cherry_mx_switch") (part "mx_switch"))
    )
    (comp (ref "SB73")
      (value "mx_switch")
      (footprint "cherry_mx_5pin_led")
      (libsource (lib "cherry_mx_switch") (part "mx_switch"))
    )
    (comp (ref "SB74")
      (value "mx_switch")
      (footprint "cherry_mx_5pin_led")
      (libsource (lib "cherry_mx_switch") (part "mx_switch"))
    )
    (comp (ref "SB75")
      (value "mx_switch")
      (footprint "cherry_mx_5pin_led")
      (libsource (lib "") (part "mx_switch_1"))
    )
    (comp (ref "SB76")
      (value "mx_switch")
      (footprint "cherry_mx_5pin_led")
      (libsource (lib "cherry_mx_switch") (part "mx_switch"))
    )
    (comp (ref "SB77")
      (value "mx_switch")
      (footprint "cherry_mx_5pin_led")
      (libsource (lib "cherry_mx_switch") (part "mx_switch"))
    )
    (comp (ref "SB78")
      (value "mx_switch")
      (footprint "cherry_mx_5pin_led")
      (libsource (lib "cherry_mx_switch") (part "mx_switch"))
    )
    (comp (ref "SB79")
      (value "mx_switch")
      (footprint "cherry_mx_5pin_led")
      (libsource (lib "cherry_mx_switch") (part "mx_switch"))
    )
    (comp (ref "SB80")
      (value "mx_switch")
      (footprint "cherry_mx_5pin_led")
      (libsource (lib "cherry_mx_switch") (part "mx_switch"))
    )
    (comp (ref "SB81")
      (value "mx_switch")
      (footprint "cherry_mx_5pin_led")
      (libsource (lib "cherry_mx_switch") (part "mx_switch"))
    )
    (comp (ref "SB82")
      (value "mx_switch")
      (footprint "cherry_mx_5pin_led")
      (libsource (lib "cherry_mx_switch") (part "mx_switch"))
    )
    (comp (ref "SB83")
      (value "mx_switch")
      (footprint "cherry_mx_5pin_led")
      (libsource (lib "cherry_mx_switch") (part "mx_switch"))
    )
    (comp (ref "SB84")
      (value "mx_switch")
      (footprint "cherry_mx_5pin_led")
      (libsource (lib "cherry_mx_switch") (part "mx_switch"))
    )
    (comp (ref "VD1")
      (value "switch_led")
      (footprint "switch_led")
      (libsource (lib "cherry_mx_switch") (part "switch_led"))
    )
    (comp (ref "VD2")
      (value "switch_led")
      (footprint "switch_led")
      (libsource (lib "cherry_mx_switch") (part "switch_led"))
    )
    (comp (ref "VD3")
      (value "switch_led")
      (footprint "switch_led")
      (libsource (lib "cherry_mx_switch") (part "switch_led"))
    )
    (comp (ref "VD4")
      (value "switch_led")
      (footprint "switch_led")
      (libsource (lib "cherry_mx_switch") (part "switch_led"))
    )
    (comp (ref "VD5")
      (value "switch_led")
      (footprint "switch_led")
      (libsource (lib "cherry_mx_switch") (part "switch_led"))
    )
    (comp (ref "VD6")
      (value "switch_led")
      (footprint "switch_led")
      (libsource (lib "cherry_mx_switch") (part "switch_led"))
    )
    (comp (ref "VD7")
      (value "switch_led")
      (footprint "switch_led")
      (libsource (lib "cherry_mx_switch") (part "switch_led"))
    )
    (comp (ref "VD8")
      (value "switch_led")
      (footprint "switch_led")
      (libsource (lib "cherry_mx_switch") (part "switch_led"))
    )
    (comp (ref "VD9")
      (value "switch_led")
      (footprint "switch_led")
      (libsource (lib "cherry_mx_switch") (part "switch_led"))
    )
    (comp (ref "VD10")
      (value "switch_led")
      (footprint "switch_led")
      (libsource (lib "cherry_mx_switch") (part "switch_led"))
    )
    (comp (ref "VD11")
      (value "switch_led")
      (footprint "switch_led")
      (libsource (lib "cherry_mx_switch") (part "switch_led"))
    )
    (comp (ref "VD12")
      (value "switch_led")
      (footprint "switch_led")
      (libsource (lib "cherry_mx_switch") (part "switch_led"))
    )
    (comp (ref "VD13")
      (value "switch_led")
      (footprint "switch_led")
      (libsource (lib "cherry_mx_switch") (part "switch_led"))
    )
    (comp (ref "VD14")
      (value "switch_led")
      (footprint "switch_led")
      (libsource (lib "cherry_mx_switch") (part "switch_led"))
    )
    (comp (ref "VD15")
      (value "VD")
      (footprint "SMB")
      (fields (field (name "PART NUMBER") "Диод 10BQ040PbF"))
      (libsource (lib "GOST") (part "VD"))
    )
    (comp (ref "VD16")
      (value "VD")
      (footprint "SMB")
      (fields (field (name "PART NUMBER") "Диод 10BQ040PbF"))
      (libsource (lib "GOST") (part "VD"))
    )
    (comp (ref "VD17")
      (value "VD")
      (footprint "SMB")
      (fields (field (name "PART NUMBER") "Диод 10BQ040PbF"))
      (libsource (lib "GOST") (part "VD"))
    )
    (comp (ref "VD18")
      (value "VD")
      (footprint "SMB")
      (fields (field (name "PART NUMBER") "Диод 10BQ040PbF"))
      (libsource (lib "GOST") (part "VD"))
    )
    (comp (ref "VD19")
      (value "VD")
      (footprint "SMB")
      (fields (field (name "PART NUMBER") "Диод 10BQ040PbF"))
      (libsource (lib "GOST") (part "VD"))
    )
    (comp (ref "VD20")
      (value "VD")
      (footprint "SMB")
      (fields (field (name "PART NUMBER") "Диод 10BQ040PbF"))
      (libsource (lib "GOST") (part "VD"))
    )
    (comp (ref "VD21")
      (value "VD")
      (footprint "SMB")
      (fields (field (name "PART NUMBER") "Диод 10BQ040PbF"))
      (libsource (lib "GOST") (part "VD"))
    )
    (comp (ref "VD22")
      (value "VD")
      (footprint "SMB")
      (fields (field (name "PART NUMBER") "Диод 10BQ040PbF"))
      (libsource (lib "GOST") (part "VD"))
    )
    (comp (ref "VD23")
      (value "VD")
      (footprint "SMB")
      (fields (field (name "PART NUMBER") "Диод 10BQ040PbF"))
      (libsource (lib "GOST") (part "VD"))
    )
    (comp (ref "VD24")
      (value "VD")
      (footprint "SMB")
      (fields (field (name "PART NUMBER") "Диод 10BQ040PbF"))
      (libsource (lib "GOST") (part "VD"))
    )
    (comp (ref "VD25")
      (value "VD")
      (footprint "SMB")
      (fields (field (name "PART NUMBER") "Диод 10BQ040PbF"))
      (libsource (lib "GOST") (part "VD"))
    )
    (comp (ref "VD26")
      (value "VD")
      (footprint "SMB")
      (fields (field (name "PART NUMBER") "Диод 10BQ040PbF"))
      (libsource (lib "GOST") (part "VD"))
    )
    (comp (ref "VD27")
      (value "VD")
      (footprint "SMB")
      (fields (field (name "PART NUMBER") "Диод 10BQ040PbF"))
      (libsource (lib "GOST") (part "VD"))
    )
    (comp (ref "VD28")
      (value "VD")
      (footprint "SMB")
      (fields (field (name "PART NUMBER") "Диод 10BQ040PbF"))
      (libsource (lib "GOST") (part "VD"))
    )
    (comp (ref "VD29")
      (value "switch_led")
      (footprint "switch_led")
      (libsource (lib "cherry_mx_switch") (part "switch_led"))
    )
    (comp (ref "VD30")
      (value "switch_led")
      (footprint "switch_led")
      (libsource (lib "cherry_mx_switch") (part "switch_led"))
    )
    (comp (ref "VD31")
      (value "switch_led")
      (footprint "switch_led")
      (libsource (lib "cherry_mx_switch") (part "switch_led"))
    )
    (comp (ref "VD32")
      (value "switch_led")
      (footprint "switch_led")
      (libsource (lib "cherry_mx_switch") (part "switch_led"))
    )
    (comp (ref "VD33")
      (value "switch_led")
      (footprint "switch_led")
      (libsource (lib "cherry_mx_switch") (part "switch_led"))
    )
    (comp (ref "VD34")
      (value "switch_led")
      (footprint "switch_led")
      (libsource (lib "cherry_mx_switch") (part "switch_led"))
    )
    (comp (ref "VD35")
      (value "switch_led")
      (footprint "switch_led")
      (libsource (lib "cherry_mx_switch") (part "switch_led"))
    )
    (comp (ref "VD36")
      (value "switch_led")
      (footprint "switch_led")
      (libsource (lib "cherry_mx_switch") (part "switch_led"))
    )
    (comp (ref "VD37")
      (value "switch_led")
      (footprint "switch_led")
      (libsource (lib "cherry_mx_switch") (part "switch_led"))
    )
    (comp (ref "VD38")
      (value "switch_led")
      (footprint "switch_led")
      (libsource (lib "cherry_mx_switch") (part "switch_led"))
    )
    (comp (ref "VD39")
      (value "switch_led")
      (footprint "switch_led")
      (libsource (lib "cherry_mx_switch") (part "switch_led"))
    )
    (comp (ref "VD40")
      (value "switch_led")
      (footprint "switch_led")
      (libsource (lib "cherry_mx_switch") (part "switch_led"))
    )
    (comp (ref "VD41")
      (value "switch_led")
      (footprint "switch_led")
      (libsource (lib "cherry_mx_switch") (part "switch_led"))
    )
    (comp (ref "VD42")
      (value "switch_led")
      (footprint "switch_led")
      (libsource (lib "cherry_mx_switch") (part "switch_led"))
    )
    (comp (ref "VD43")
      (value "VD")
      (footprint "SMB")
      (fields (field (name "PART NUMBER") "Диод 10BQ040PbF"))
      (libsource (lib "GOST") (part "VD"))
    )
    (comp (ref "VD44")
      (value "VD")
      (footprint "SMB")
      (fields (field (name "PART NUMBER") "Диод 10BQ040PbF"))
      (libsource (lib "GOST") (part "VD"))
    )
    (comp (ref "VD45")
      (value "VD")
      (footprint "SMB")
      (fields (field (name "PART NUMBER") "Диод 10BQ040PbF"))
      (libsource (lib "GOST") (part "VD"))
    )
    (comp (ref "VD46")
      (value "VD")
      (footprint "SMB")
      (fields (field (name "PART NUMBER") "Диод 10BQ040PbF"))
      (libsource (lib "GOST") (part "VD"))
    )
    (comp (ref "VD47")
      (value "VD")
      (footprint "SMB")
      (fields (field (name "PART NUMBER") "Диод 10BQ040PbF"))
      (libsource (lib "GOST") (part "VD"))
    )
    (comp (ref "VD48")
      (value "VD")
      (footprint "SMB")
      (fields (field (name "PART NUMBER") "Диод 10BQ040PbF"))
      (libsource (lib "GOST") (part "VD"))
    )
    (comp (ref "VD49")
      (value "VD")
      (footprint "SMB")
      (fields (field (name "PART NUMBER") "Диод 10BQ040PbF"))
      (libsource (lib "GOST") (part "VD"))
    )
    (comp (ref "VD50")
      (value "VD")
      (footprint "SMB")
      (fields (field (name "PART NUMBER") "Диод 10BQ040PbF"))
      (libsource (lib "GOST") (part "VD"))
    )
    (comp (ref "VD51")
      (value "VD")
      (footprint "SMB")
      (fields (field (name "PART NUMBER") "Диод 10BQ040PbF"))
      (libsource (lib "GOST") (part "VD"))
    )
    (comp (ref "VD52")
      (value "VD")
      (footprint "SMB")
      (fields (field (name "PART NUMBER") "Диод 10BQ040PbF"))
      (libsource (lib "GOST") (part "VD"))
    )
    (comp (ref "VD53")
      (value "VD")
      (footprint "SMB")
      (fields (field (name "PART NUMBER") "Диод 10BQ040PbF"))
      (libsource (lib "GOST") (part "VD"))
    )
    (comp (ref "VD54")
      (value "VD")
      (footprint "SMB")
      (fields (field (name "PART NUMBER") "Диод 10BQ040PbF"))
      (libsource (lib "GOST") (part "VD"))
    )
    (comp (ref "VD55")
      (value "VD")
      (footprint "SMB")
      (fields (field (name "PART NUMBER") "Диод 10BQ040PbF"))
      (libsource (lib "GOST") (part "VD"))
    )
    (comp (ref "VD56")
      (value "VD")
      (footprint "SMB")
      (fields (field (name "PART NUMBER") "Диод 10BQ040PbF"))
      (libsource (lib "GOST") (part "VD"))
    )
    (comp (ref "VD57")
      (value "switch_led")
      (footprint "switch_led")
      (libsource (lib "cherry_mx_switch") (part "switch_led"))
    )
    (comp (ref "VD58")
      (value "switch_led")
      (footprint "switch_led")
      (libsource (lib "cherry_mx_switch") (part "switch_led"))
    )
    (comp (ref "VD59")
      (value "switch_led")
      (footprint "switch_led")
      (libsource (lib "cherry_mx_switch") (part "switch_led"))
    )
    (comp (ref "VD60")
      (value "switch_led")
      (footprint "switch_led")
      (libsource (lib "cherry_mx_switch") (part "switch_led"))
    )
    (comp (ref "VD61")
      (value "switch_led")
      (footprint "switch_led")
      (libsource (lib "cherry_mx_switch") (part "switch_led"))
    )
    (comp (ref "VD62")
      (value "switch_led")
      (footprint "switch_led")
      (libsource (lib "cherry_mx_switch") (part "switch_led"))
    )
    (comp (ref "VD63")
      (value "switch_led")
      (footprint "switch_led")
      (libsource (lib "cherry_mx_switch") (part "switch_led"))
    )
    (comp (ref "VD64")
      (value "switch_led")
      (footprint "switch_led")
      (libsource (lib "cherry_mx_switch") (part "switch_led"))
    )
    (comp (ref "VD65")
      (value "switch_led")
      (footprint "switch_led")
      (libsource (lib "cherry_mx_switch") (part "switch_led"))
    )
    (comp (ref "VD66")
      (value "switch_led")
      (footprint "switch_led")
      (libsource (lib "cherry_mx_switch") (part "switch_led"))
    )
    (comp (ref "VD67")
      (value "switch_led")
      (footprint "switch_led")
      (libsource (lib "cherry_mx_switch") (part "switch_led"))
    )
    (comp (ref "VD68")
      (value "switch_led")
      (footprint "switch_led")
      (libsource (lib "cherry_mx_switch") (part "switch_led"))
    )
    (comp (ref "VD69")
      (value "switch_led")
      (footprint "switch_led")
      (libsource (lib "cherry_mx_switch") (part "switch_led"))
    )
    (comp (ref "VD70")
      (value "switch_led")
      (footprint "switch_led")
      (libsource (lib "cherry_mx_switch") (part "switch_led"))
    )
    (comp (ref "VD71")
      (value "VD")
      (footprint "SMB")
      (fields (field (name "PART NUMBER") "Диод 10BQ040PbF"))
      (libsource (lib "GOST") (part "VD"))
    )
    (comp (ref "VD72")
      (value "VD")
      (footprint "SMB")
      (fields (field (name "PART NUMBER") "Диод 10BQ040PbF"))
      (libsource (lib "GOST") (part "VD"))
    )
    (comp (ref "VD73")
      (value "VD")
      (footprint "SMB")
      (fields (field (name "PART NUMBER") "Диод 10BQ040PbF"))
      (libsource (lib "GOST") (part "VD"))
    )
    (comp (ref "VD74")
      (value "VD")
      (footprint "SMB")
      (fields (field (name "PART NUMBER") "Диод 10BQ040PbF"))
      (libsource (lib "GOST") (part "VD"))
    )
    (comp (ref "VD75")
      (value "VD")
      (footprint "SMB")
      (fields (field (name "PART NUMBER") "Диод 10BQ040PbF"))
      (libsource (lib "GOST") (part "VD"))
    )
    (comp (ref "VD76")
      (value "VD")
      (footprint "SMB")
      (fields (field (name "PART NUMBER") "Диод 10BQ040PbF"))
      (libsource (lib "GOST") (part "VD"))
    )
    (comp (ref "VD77")
      (value "VD")
      (footprint "SMB")
      (fields (field (name "PART NUMBER") "Диод 10BQ040PbF"))
      (libsource (lib "GOST") (part "VD"))
    )
    (comp (ref "VD78")
      (value "VD")
      (footprint "SMB")
      (fields (field (name "PART NUMBER") "Диод 10BQ040PbF"))
      (libsource (lib "GOST") (part "VD"))
    )
    (comp (ref "VD79")
      (value "VD")
      (footprint "SMB")
      (fields (field (name "PART NUMBER") "Диод 10BQ040PbF"))
      (libsource (lib "GOST") (part "VD"))
    )
    (comp (ref "VD80")
      (value "VD")
      (footprint "SMB")
      (fields (field (name "PART NUMBER") "Диод 10BQ040PbF"))
      (libsource (lib "GOST") (part "VD"))
    )
    (comp (ref "VD81")
      (value "VD")
      (footprint "SMB")
      (fields (field (name "PART NUMBER") "Диод 10BQ040PbF"))
      (libsource (lib "GOST") (part "VD"))
    )
    (comp (ref "VD82")
      (value "VD")
      (footprint "SMB")
      (fields (field (name "PART NUMBER") "Диод 10BQ040PbF"))
      (libsource (lib "GOST") (part "VD"))
    )
    (comp (ref "VD83")
      (value "VD")
      (footprint "SMB")
      (fields (field (name "PART NUMBER") "Диод 10BQ040PbF"))
      (libsource (lib "GOST") (part "VD"))
    )
    (comp (ref "VD84")
      (value "VD")
      (footprint "SMB")
      (fields (field (name "PART NUMBER") "Диод 10BQ040PbF"))
      (libsource (lib "GOST") (part "VD"))
    )
    (comp (ref "VD85")
      (value "switch_led")
      (footprint "switch_led")
      (libsource (lib "cherry_mx_switch") (part "switch_led"))
    )
    (comp (ref "VD86")
      (value "switch_led")
      (footprint "switch_led")
      (libsource (lib "cherry_mx_switch") (part "switch_led"))
    )
    (comp (ref "VD87")
      (value "switch_led")
      (footprint "switch_led")
      (libsource (lib "cherry_mx_switch") (part "switch_led"))
    )
    (comp (ref "VD88")
      (value "switch_led")
      (footprint "switch_led")
      (libsource (lib "cherry_mx_switch") (part "switch_led"))
    )
    (comp (ref "VD89")
      (value "switch_led")
      (footprint "switch_led")
      (libsource (lib "cherry_mx_switch") (part "switch_led"))
    )
    (comp (ref "VD90")
      (value "switch_led")
      (footprint "switch_led")
      (libsource (lib "cherry_mx_switch") (part "switch_led"))
    )
    (comp (ref "VD91")
      (value "switch_led")
      (footprint "switch_led")
      (libsource (lib "cherry_mx_switch") (part "switch_led"))
    )
    (comp (ref "VD92")
      (value "switch_led")
      (footprint "switch_led")
      (libsource (lib "cherry_mx_switch") (part "switch_led"))
    )
    (comp (ref "VD93")
      (value "switch_led")
      (footprint "switch_led")
      (libsource (lib "cherry_mx_switch") (part "switch_led"))
    )
    (comp (ref "VD94")
      (value "switch_led")
      (footprint "switch_led")
      (libsource (lib "cherry_mx_switch") (part "switch_led"))
    )
    (comp (ref "VD95")
      (value "switch_led")
      (footprint "switch_led")
      (libsource (lib "cherry_mx_switch") (part "switch_led"))
    )
    (comp (ref "VD96")
      (value "switch_led")
      (footprint "switch_led")
      (libsource (lib "cherry_mx_switch") (part "switch_led"))
    )
    (comp (ref "VD97")
      (value "switch_led")
      (footprint "switch_led")
      (libsource (lib "cherry_mx_switch") (part "switch_led"))
    )
    (comp (ref "VD98")
      (value "switch_led")
      (footprint "switch_led")
      (libsource (lib "cherry_mx_switch") (part "switch_led"))
    )
    (comp (ref "VD99")
      (value "VD")
      (footprint "SMB")
      (fields (field (name "PART NUMBER") "Диод 10BQ040PbF"))
      (libsource (lib "GOST") (part "VD"))
    )
    (comp (ref "VD100")
      (value "VD")
      (footprint "SMB")
      (fields (field (name "PART NUMBER") "Диод 10BQ040PbF"))
      (libsource (lib "GOST") (part "VD"))
    )
    (comp (ref "VD101")
      (value "VD")
      (footprint "SMB")
      (fields (field (name "PART NUMBER") "Диод 10BQ040PbF"))
      (libsource (lib "GOST") (part "VD"))
    )
    (comp (ref "VD102")
      (value "VD")
      (footprint "SMB")
      (fields (field (name "PART NUMBER") "Диод 10BQ040PbF"))
      (libsource (lib "GOST") (part "VD"))
    )
    (comp (ref "VD103")
      (value "VD")
      (footprint "SMB")
      (fields (field (name "PART NUMBER") "Диод 10BQ040PbF"))
      (libsource (lib "GOST") (part "VD"))
    )
    (comp (ref "VD104")
      (value "VD")
      (footprint "SMB")
      (fields (field (name "PART NUMBER") "Диод 10BQ040PbF"))
      (libsource (lib "GOST") (part "VD"))
    )
    (comp (ref "VD105")
      (value "VD")
      (footprint "SMB")
      (fields (field (name "PART NUMBER") "Диод 10BQ040PbF"))
      (libsource (lib "GOST") (part "VD"))
    )
    (comp (ref "VD106")
      (value "VD")
      (footprint "SMB")
      (fields (field (name "PART NUMBER") "Диод 10BQ040PbF"))
      (libsource (lib "GOST") (part "VD"))
    )
    (comp (ref "VD107")
      (value "VD")
      (footprint "SMB")
      (fields (field (name "PART NUMBER") "Диод 10BQ040PbF"))
      (libsource (lib "GOST") (part "VD"))
    )
    (comp (ref "VD108")
      (value "VD")
      (footprint "SMB")
      (fields (field (name "PART NUMBER") "Диод 10BQ040PbF"))
      (libsource (lib "GOST") (part "VD"))
    )
    (comp (ref "VD109")
      (value "VD")
      (footprint "SMB")
      (fields (field (name "PART NUMBER") "Диод 10BQ040PbF"))
      (libsource (lib "GOST") (part "VD"))
    )
    (comp (ref "VD110")
      (value "VD")
      (footprint "SMB")
      (fields (field (name "PART NUMBER") "Диод 10BQ040PbF"))
      (libsource (lib "GOST") (part "VD"))
    )
    (comp (ref "VD111")
      (value "VD")
      (footprint "SMB")
      (fields (field (name "PART NUMBER") "Диод 10BQ040PbF"))
      (libsource (lib "GOST") (part "VD"))
    )
    (comp (ref "VD112")
      (value "VD")
      (footprint "SMB")
      (fields (field (name "PART NUMBER") "Диод 10BQ040PbF"))
      (libsource (lib "GOST") (part "VD"))
    )
    (comp (ref "VD113")
      (value "switch_led")
      (footprint "switch_led")
      (libsource (lib "cherry_mx_switch") (part "switch_led"))
    )
    (comp (ref "VD114")
      (value "switch_led")
      (footprint "switch_led")
      (libsource (lib "cherry_mx_switch") (part "switch_led"))
    )
    (comp (ref "VD115")
      (value "switch_led")
      (footprint "switch_led")
      (libsource (lib "cherry_mx_switch") (part "switch_led"))
    )
    (comp (ref "VD116")
      (value "switch_led")
      (footprint "switch_led")
      (libsource (lib "cherry_mx_switch") (part "switch_led"))
    )
    (comp (ref "VD117")
      (value "switch_led")
      (footprint "switch_led")
      (libsource (lib "cherry_mx_switch") (part "switch_led"))
    )
    (comp (ref "VD118")
      (value "switch_led")
      (footprint "switch_led")
      (libsource (lib "cherry_mx_switch") (part "switch_led"))
    )
    (comp (ref "VD119")
      (value "switch_led")
      (footprint "switch_led")
      (libsource (lib "cherry_mx_switch") (part "switch_led"))
    )
    (comp (ref "VD120")
      (value "switch_led")
      (footprint "switch_led")
      (libsource (lib "cherry_mx_switch") (part "switch_led"))
    )
    (comp (ref "VD121")
      (value "switch_led")
      (footprint "switch_led")
      (libsource (lib "cherry_mx_switch") (part "switch_led"))
    )
    (comp (ref "VD122")
      (value "switch_led")
      (footprint "switch_led")
      (libsource (lib "cherry_mx_switch") (part "switch_led"))
    )
    (comp (ref "VD123")
      (value "switch_led")
      (footprint "switch_led")
      (libsource (lib "cherry_mx_switch") (part "switch_led"))
    )
    (comp (ref "VD124")
      (value "switch_led")
      (footprint "switch_led")
      (libsource (lib "cherry_mx_switch") (part "switch_led"))
    )
    (comp (ref "VD125")
      (value "switch_led")
      (footprint "switch_led")
      (libsource (lib "cherry_mx_switch") (part "switch_led"))
    )
    (comp (ref "VD126")
      (value "switch_led")
      (footprint "switch_led")
      (libsource (lib "cherry_mx_switch") (part "switch_led"))
    )
    (comp (ref "VD127")
      (value "VD")
      (footprint "SMB")
      (fields (field (name "PART NUMBER") "Диод 10BQ040PbF"))
      (libsource (lib "GOST") (part "VD"))
    )
    (comp (ref "VD128")
      (value "VD")
      (footprint "SMB")
      (fields (field (name "PART NUMBER") "Диод 10BQ040PbF"))
      (libsource (lib "GOST") (part "VD"))
    )
    (comp (ref "VD129")
      (value "VD")
      (footprint "SMB")
      (fields (field (name "PART NUMBER") "Диод 10BQ040PbF"))
      (libsource (lib "GOST") (part "VD"))
    )
    (comp (ref "VD130")
      (value "VD")
      (footprint "SMB")
      (fields (field (name "PART NUMBER") "Диод 10BQ040PbF"))
      (libsource (lib "GOST") (part "VD"))
    )
    (comp (ref "VD131")
      (value "VD")
      (footprint "SMB")
      (fields (field (name "PART NUMBER") "Диод 10BQ040PbF"))
      (libsource (lib "GOST") (part "VD"))
    )
    (comp (ref "VD132")
      (value "VD")
      (footprint "SMB")
      (fields (field (name "PART NUMBER") "Диод 10BQ040PbF"))
      (libsource (lib "GOST") (part "VD"))
    )
    (comp (ref "VD133")
      (value "VD")
      (footprint "SMB")
      (fields (field (name "PART NUMBER") "Диод 10BQ040PbF"))
      (libsource (lib "GOST") (part "VD"))
    )
    (comp (ref "VD134")
      (value "VD")
      (footprint "SMB")
      (fields (field (name "PART NUMBER") "Диод 10BQ040PbF"))
      (libsource (lib "GOST") (part "VD"))
    )
    (comp (ref "VD135")
      (value "VD")
      (footprint "SMB")
      (fields (field (name "PART NUMBER") "Диод 10BQ040PbF"))
      (libsource (lib "GOST") (part "VD"))
    )
    (comp (ref "VD136")
      (value "VD")
      (footprint "SMB")
      (fields (field (name "PART NUMBER") "Диод 10BQ040PbF"))
      (libsource (lib "GOST") (part "VD"))
    )
    (comp (ref "VD137")
      (value "VD")
      (footprint "SMB")
      (fields (field (name "PART NUMBER") "Диод 10BQ040PbF"))
      (libsource (lib "GOST") (part "VD"))
    )
    (comp (ref "VD138")
      (value "VD")
      (footprint "SMB")
      (fields (field (name "PART NUMBER") "Диод 10BQ040PbF"))
      (libsource (lib "GOST") (part "VD"))
    )
    (comp (ref "VD139")
      (value "VD")
      (footprint "SMB")
      (fields (field (name "PART NUMBER") "Диод 10BQ040PbF"))
      (libsource (lib "GOST") (part "VD"))
    )
    (comp (ref "VD140")
      (value "VD")
      (footprint "SMB")
      (fields (field (name "PART NUMBER") "Диод 10BQ040PbF"))
      (libsource (lib "GOST") (part "VD"))
    )
    (comp (ref "VD141")
      (value "switch_led")
      (footprint "switch_led")
      (libsource (lib "cherry_mx_switch") (part "switch_led"))
    )
    (comp (ref "VD142")
      (value "switch_led")
      (footprint "switch_led")
      (libsource (lib "cherry_mx_switch") (part "switch_led"))
    )
    (comp (ref "VD143")
      (value "switch_led")
      (footprint "switch_led")
      (libsource (lib "cherry_mx_switch") (part "switch_led"))
    )
    (comp (ref "VD144")
      (value "switch_led")
      (footprint "switch_led")
      (libsource (lib "cherry_mx_switch") (part "switch_led"))
    )
    (comp (ref "VD145")
      (value "switch_led")
      (footprint "switch_led")
      (libsource (lib "cherry_mx_switch") (part "switch_led"))
    )
    (comp (ref "VD146")
      (value "switch_led")
      (footprint "switch_led")
      (libsource (lib "cherry_mx_switch") (part "switch_led"))
    )
    (comp (ref "VD147")
      (value "switch_led")
      (footprint "switch_led")
      (libsource (lib "cherry_mx_switch") (part "switch_led"))
    )
    (comp (ref "VD148")
      (value "switch_led")
      (footprint "switch_led")
      (libsource (lib "cherry_mx_switch") (part "switch_led"))
    )
    (comp (ref "VD149")
      (value "switch_led")
      (footprint "switch_led")
      (libsource (lib "cherry_mx_switch") (part "switch_led"))
    )
    (comp (ref "VD150")
      (value "switch_led")
      (footprint "switch_led")
      (libsource (lib "cherry_mx_switch") (part "switch_led"))
    )
    (comp (ref "VD151")
      (value "switch_led")
      (footprint "switch_led")
      (libsource (lib "cherry_mx_switch") (part "switch_led"))
    )
    (comp (ref "VD152")
      (value "switch_led")
      (footprint "switch_led")
      (libsource (lib "cherry_mx_switch") (part "switch_led"))
    )
    (comp (ref "VD153")
      (value "switch_led")
      (footprint "switch_led")
      (libsource (lib "cherry_mx_switch") (part "switch_led"))
    )
    (comp (ref "VD154")
      (value "switch_led")
      (footprint "switch_led")
      (libsource (lib "cherry_mx_switch") (part "switch_led"))
    )
    (comp (ref "VD155")
      (value "VD")
      (footprint "SMB")
      (fields (field (name "PART NUMBER") "Диод 10BQ040PbF"))
      (libsource (lib "GOST") (part "VD"))
    )
    (comp (ref "VD156")
      (value "VD")
      (footprint "SMB")
      (fields (field (name "PART NUMBER") "Диод 10BQ040PbF"))
      (libsource (lib "GOST") (part "VD"))
    )
    (comp (ref "VD157")
      (value "VD")
      (footprint "SMB")
      (fields (field (name "PART NUMBER") "Диод 10BQ040PbF"))
      (libsource (lib "GOST") (part "VD"))
    )
    (comp (ref "VD158")
      (value "VD")
      (footprint "SMB")
      (fields (field (name "PART NUMBER") "Диод 10BQ040PbF"))
      (libsource (lib "GOST") (part "VD"))
    )
    (comp (ref "VD159")
      (value "VD")
      (footprint "SMB")
      (fields (field (name "PART NUMBER") "Диод 10BQ040PbF"))
      (libsource (lib "GOST") (part "VD"))
    )
    (comp (ref "VD160")
      (value "VD")
      (footprint "SMB")
      (fields (field (name "PART NUMBER") "Диод 10BQ040PbF"))
      (libsource (lib "GOST") (part "VD"))
    )
    (comp (ref "VD161")
      (value "VD")
      (footprint "SMB")
      (fields (field (name "PART NUMBER") "Диод 10BQ040PbF"))
      (libsource (lib "GOST") (part "VD"))
    )
    (comp (ref "VD162")
      (value "VD")
      (footprint "SMB")
      (fields (field (name "PART NUMBER") "Диод 10BQ040PbF"))
      (libsource (lib "GOST") (part "VD"))
    )
    (comp (ref "VD163")
      (value "VD")
      (footprint "SMB")
      (fields (field (name "PART NUMBER") "Диод 10BQ040PbF"))
      (libsource (lib "GOST") (part "VD"))
    )
    (comp (ref "VD164")
      (value "VD")
      (footprint "SMB")
      (fields (field (name "PART NUMBER") "Диод 10BQ040PbF"))
      (libsource (lib "GOST") (part "VD"))
    )
    (comp (ref "VD165")
      (value "VD")
      (footprint "SMB")
      (fields (field (name "PART NUMBER") "Диод 10BQ040PbF"))
      (libsource (lib "GOST") (part "VD"))
    )
    (comp (ref "VD166")
      (value "VD")
      (footprint "SMB")
      (fields (field (name "PART NUMBER") "Диод 10BQ040PbF"))
      (libsource (lib "GOST") (part "VD"))
    )
    (comp (ref "VD167")
      (value "VD")
      (footprint "SMB")
      (fields (field (name "PART NUMBER") "Диод 10BQ040PbF"))
      (libsource (lib "GOST") (part "VD"))
    )
    (comp (ref "VD168")
      (value "VD")
      (footprint "SMB")
      (fields (field (name "PART NUMBER") "Диод 10BQ040PbF"))
      (libsource (lib "GOST") (part "VD"))
    )
    (comp (ref "X1")
      (value "X_1")
      (footprint "ZFKDSA_1,5-W-7,62")
      (fields (field (name "PART NUMBER") "Колодка клеммная ZFKDSA 1,5-W-7,62"))
      (libsource (lib "GOST") (part "X_1"))
    )
    (comp (ref "X2")
      (value "X_6")
      (footprint "1734753-1")
      (fields (field (name "PART NUMBER") "Розетка 1734753-1"))
      (libsource (lib "GOST") (part "X_6"))
    )
    (comp (ref "X3")
      (value "X_14")
      (footprint "BH-14")
      (fields (field (name "PART NUMBER") "Вилка BH-14"))
      (libsource (lib "GOST") (part "X_14"))
    )
  )
  (nets
    (net (code "1") (name "+5") (class "Default")
      (node (ref "R1") (pin "2") (pinfunction "2_2") (pintype "passive"))
      (node (ref "R10") (pin "2") (pinfunction "2_2") (pintype "passive"))
      (node (ref "R11") (pin "2") (pinfunction "2_2") (pintype "passive"))
      (node (ref "R12") (pin "2") (pinfunction "2_2") (pintype "passive"))
      (node (ref "R13") (pin "2") (pinfunction "2_2") (pintype "passive"))
      (node (ref "R14") (pin "2") (pinfunction "2_2") (pintype "passive"))
      (node (ref "R15") (pin "1") (pinfunction "1_1") (pintype "passive"))
      (node (ref "R16") (pin "2") (pinfunction "2_2") (pintype "passive"))
      (node (ref "R17") (pin "2") (pinfunction "2_2") (pintype "passive"))
      (node (ref "R18") (pin "2") (pinfunction "2_2") (pintype "passive"))
      (node (ref "R19") (pin "2") (pinfunction "2_2") (pintype "passive"))
      (node (ref "R2") (pin "2") (pinfunction "2_2") (pintype "passive"))
      (node (ref "R20") (pin "2") (pinfunction "2_2") (pintype "passive"))
      (node (ref "R21") (pin "2") (pinfunction "2_2") (pintype "passive"))
      (node (ref "R22") (pin "2") (pinfunction "2_2") (pintype "passive"))
      (node (ref "R23") (pin "2") (pinfunction "2_2") (pintype "passive"))
      (node (ref "R24") (pin "2") (pinfunction "2_2") (pintype "passive"))
      (node (ref "R25") (pin "2") (pinfunction "2_2") (pintype "passive"))
      (node (ref "R26") (pin "2") (pinfunction "2_2") (pintype "passive"))
      (node (ref "R27") (pin "2") (pinfunction "2_2") (pintype "passive"))
      (node (ref "R28") (pin "2") (pinfunction "2_2") (pintype "passive"))
      (node (ref "R29") (pin "2") (pinfunction "2_2") (pintype "passive"))
      (node (ref "R3") (pin "2") (pinfunction "2_2") (pintype "passive"))
      (node (ref "R30") (pin "1") (pinfunction "1_1") (pintype "passive"))
      (node (ref "R31") (pin "2") (pinfunction "2_2") (pintype "passive"))
      (node (ref "R32") (pin "2") (pinfunction "2_2") (pintype "passive"))
      (node (ref "R33") (pin "2") (pinfunction "2_2") (pintype "passive"))
      (node (ref "R34") (pin "2") (pinfunction "2_2") (pintype "passive"))
      (node (ref "R35") (pin "2") (pinfunction "2_2") (pintype "passive"))
      (node (ref "R36") (pin "2") (pinfunction "2_2") (pintype "passive"))
      (node (ref "R37") (pin "2") (pinfunction "2_2") (pintype "passive"))
      (node (ref "R38") (pin "2") (pinfunction "2_2") (pintype "passive"))
      (node (ref "R39") (pin "2") (pinfunction "2_2") (pintype "passive"))
      (node (ref "R4") (pin "2") (pinfunction "2_2") (pintype "passive"))
      (node (ref "R40") (pin "2") (pinfunction "2_2") (pintype "passive"))
      (node (ref "R41") (pin "2") (pinfunction "2_2") (pintype "passive"))
      (node (ref "R42") (pin "2") (pinfunction "2_2") (pintype "passive"))
      (node (ref "R43") (pin "2") (pinfunction "2_2") (pintype "passive"))
      (node (ref "R44") (pin "2") (pinfunction "2_2") (pintype "passive"))
      (node (ref "R45") (pin "1") (pinfunction "1_1") (pintype "passive"))
      (node (ref "R46") (pin "2") (pinfunction "2_2") (pintype "passive"))
      (node (ref "R47") (pin "2") (pinfunction "2_2") (pintype "passive"))
      (node (ref "R48") (pin "2") (pinfunction "2_2") (pintype "passive"))
      (node (ref "R49") (pin "2") (pinfunction "2_2") (pintype "passive"))
      (node (ref "R5") (pin "2") (pinfunction "2_2") (pintype "passive"))
      (node (ref "R50") (pin "2") (pinfunction "2_2") (pintype "passive"))
      (node (ref "R51") (pin "2") (pinfunction "2_2") (pintype "passive"))
      (node (ref "R52") (pin "2") (pinfunction "2_2") (pintype "passive"))
      (node (ref "R53") (pin "2") (pinfunction "2_2") (pintype "passive"))
      (node (ref "R54") (pin "2") (pinfunction "2_2") (pintype "passive"))
      (node (ref "R55") (pin "2") (pinfunction "2_2") (pintype "passive"))
      (node (ref "R56") (pin "2") (pinfunction "2_2") (pintype "passive"))
      (node (ref "R57") (pin "2") (pinfunction "2_2") (pintype "passive"))
      (node (ref "R58") (pin "2") (pinfunction "2_2") (pintype "passive"))
      (node (ref "R59") (pin "2") (pinfunction "2_2") (pintype "passive"))
      (node (ref "R6") (pin "2") (pinfunction "2_2") (pintype "passive"))
      (node (ref "R60") (pin "1") (pinfunction "1_1") (pintype "passive"))
      (node (ref "R61") (pin "2") (pinfunction "2_2") (pintype "passive"))
      (node (ref "R62") (pin "2") (pinfunction "2_2") (pintype "passive"))
      (node (ref "R63") (pin "2") (pinfunction "2_2") (pintype "passive"))
      (node (ref "R64") (pin "2") (pinfunction "2_2") (pintype "passive"))
      (node (ref "R65") (pin "2") (pinfunction "2_2") (pintype "passive"))
      (node (ref "R66") (pin "2") (pinfunction "2_2") (pintype "passive"))
      (node (ref "R67") (pin "2") (pinfunction "2_2") (pintype "passive"))
      (node (ref "R68") (pin "2") (pinfunction "2_2") (pintype "passive"))
      (node (ref "R69") (pin "2") (pinfunction "2_2") (pintype "passive"))
      (node (ref "R7") (pin "2") (pinfunction "2_2") (pintype "passive"))
      (node (ref "R70") (pin "2") (pinfunction "2_2") (pintype "passive"))
      (node (ref "R71") (pin "2") (pinfunction "2_2") (pintype "passive"))
      (node (ref "R72") (pin "2") (pinfunction "2_2") (pintype "passive"))
      (node (ref "R73") (pin "2") (pinfunction "2_2") (pintype "passive"))
      (node (ref "R74") (pin "2") (pinfunction "2_2") (pintype "passive"))
      (node (ref "R75") (pin "1") (pinfunction "1_1") (pintype "passive"))
      (node (ref "R76") (pin "2") (pinfunction "2_2") (pintype "passive"))
      (node (ref "R77") (pin "2") (pinfunction "2_2") (pintype "passive"))
      (node (ref "R78") (pin "2") (pinfunction "2_2") (pintype "passive"))
      (node (ref "R79") (pin "2") (pinfunction "2_2") (pintype "passive"))
      (node (ref "R8") (pin "2") (pinfunction "2_2") (pintype "passive"))
      (node (ref "R80") (pin "2") (pinfunction "2_2") (pintype "passive"))
      (node (ref "R81") (pin "2") (pinfunction "2_2") (pintype "passive"))
      (node (ref "R82") (pin "2") (pinfunction "2_2") (pintype "passive"))
      (node (ref "R83") (pin "2") (pinfunction "2_2") (pintype "passive"))
      (node (ref "R84") (pin "2") (pinfunction "2_2") (pintype "passive"))
      (node (ref "R85") (pin "2") (pinfunction "2_2") (pintype "passive"))
      (node (ref "R86") (pin "2") (pinfunction "2_2") (pintype "passive"))
      (node (ref "R87") (pin "2") (pinfunction "2_2") (pintype "passive"))
      (node (ref "R88") (pin "2") (pinfunction "2_2") (pintype "passive"))
      (node (ref "R89") (pin "2") (pinfunction "2_2") (pintype "passive"))
      (node (ref "R9") (pin "2") (pinfunction "2_2") (pintype "passive"))
      (node (ref "R90") (pin "1") (pinfunction "1_1") (pintype "passive"))
    )
    (net (code "2") (name "Net-(R1-Pad1)") (class "Default")
      (node (ref "R1") (pin "1") (pinfunction "1_1") (pintype "passive"))
      (node (ref "VD1") (pin "3") (pinfunction "3_3") (pintype "passive"))
    )
    (net (code "3") (name "Net-(R2-Pad1)") (class "Default")
      (node (ref "R2") (pin "1") (pinfunction "1_1") (pintype "passive"))
      (node (ref "VD2") (pin "3") (pinfunction "3_3") (pintype "passive"))
    )
    (net (code "4") (name "Net-(R3-Pad1)") (class "Default")
      (node (ref "R3") (pin "1") (pinfunction "1_1") (pintype "passive"))
      (node (ref "VD3") (pin "3") (pinfunction "3_3") (pintype "passive"))
    )
    (net (code "5") (name "Net-(R4-Pad1)") (class "Default")
      (node (ref "R4") (pin "1") (pinfunction "1_1") (pintype "passive"))
      (node (ref "VD4") (pin "3") (pinfunction "3_3") (pintype "passive"))
    )
    (net (code "6") (name "Net-(R5-Pad1)") (class "Default")
      (node (ref "R5") (pin "1") (pinfunction "1_1") (pintype "passive"))
      (node (ref "VD5") (pin "3") (pinfunction "3_3") (pintype "passive"))
    )
    (net (code "7") (name "Net-(R6-Pad1)") (class "Default")
      (node (ref "R6") (pin "1") (pinfunction "1_1") (pintype "passive"))
      (node (ref "VD6") (pin "3") (pinfunction "3_3") (pintype "passive"))
    )
    (net (code "8") (name "Net-(R7-Pad1)") (class "Default")
      (node (ref "R7") (pin "1") (pinfunction "1_1") (pintype "passive"))
      (node (ref "VD7") (pin "3") (pinfunction "3_3") (pintype "passive"))
    )
    (net (code "9") (name "Net-(R8-Pad1)") (class "Default")
      (node (ref "R8") (pin "1") (pinfunction "1_1") (pintype "passive"))
      (node (ref "VD8") (pin "3") (pinfunction "3_3") (pintype "passive"))
    )
    (net (code "10") (name "Net-(R9-Pad1)") (class "Default")
      (node (ref "R9") (pin "1") (pinfunction "1_1") (pintype "passive"))
      (node (ref "VD9") (pin "3") (pinfunction "3_3") (pintype "passive"))
    )
    (net (code "11") (name "Net-(R10-Pad1)") (class "Default")
      (node (ref "R10") (pin "1") (pinfunction "1_1") (pintype "passive"))
      (node (ref "VD10") (pin "3") (pinfunction "3_3") (pintype "passive"))
    )
    (net (code "12") (name "Net-(R11-Pad1)") (class "Default")
      (node (ref "R11") (pin "1") (pinfunction "1_1") (pintype "passive"))
      (node (ref "VD11") (pin "3") (pinfunction "3_3") (pintype "passive"))
    )
    (net (code "13") (name "Net-(R12-Pad1)") (class "Default")
      (node (ref "R12") (pin "1") (pinfunction "1_1") (pintype "passive"))
      (node (ref "VD12") (pin "3") (pinfunction "3_3") (pintype "passive"))
    )
    (net (code "14") (name "Net-(R13-Pad1)") (class "Default")
      (node (ref "R13") (pin "1") (pinfunction "1_1") (pintype "passive"))
      (node (ref "VD13") (pin "3") (pinfunction "3_3") (pintype "passive"))
    )
    (net (code "15") (name "Net-(R14-Pad1)") (class "Default")
      (node (ref "R14") (pin "1") (pinfunction "1_1") (pintype "passive"))
      (node (ref "VD14") (pin "3") (pinfunction "3_3") (pintype "passive"))
    )
    (net (code "16") (name "Net-(R16-Pad1)") (class "Default")
      (node (ref "R16") (pin "1") (pinfunction "1_1") (pintype "passive"))
      (node (ref "VD29") (pin "3") (pinfunction "3_3") (pintype "passive"))
    )
    (net (code "17") (name "Net-(R17-Pad1)") (class "Default")
      (node (ref "R17") (pin "1") (pinfunction "1_1") (pintype "passive"))
      (node (ref "VD30") (pin "3") (pinfunction "3_3") (pintype "passive"))
    )
    (net (code "18") (name "Net-(R18-Pad1)") (class "Default")
      (node (ref "R18") (pin "1") (pinfunction "1_1") (pintype "passive"))
      (node (ref "VD31") (pin "3") (pinfunction "3_3") (pintype "passive"))
    )
    (net (code "19") (name "Net-(R19-Pad1)") (class "Default")
      (node (ref "R19") (pin "1") (pinfunction "1_1") (pintype "passive"))
      (node (ref "VD32") (pin "3") (pinfunction "3_3") (pintype "passive"))
    )
    (net (code "20") (name "Net-(R20-Pad1)") (class "Default")
      (node (ref "R20") (pin "1") (pinfunction "1_1") (pintype "passive"))
      (node (ref "VD33") (pin "3") (pinfunction "3_3") (pintype "passive"))
    )
    (net (code "21") (name "Net-(R21-Pad1)") (class "Default")
      (node (ref "R21") (pin "1") (pinfunction "1_1") (pintype "passive"))
      (node (ref "VD34") (pin "3") (pinfunction "3_3") (pintype "passive"))
    )
    (net (code "22") (name "Net-(R22-Pad1)") (class "Default")
      (node (ref "R22") (pin "1") (pinfunction "1_1") (pintype "passive"))
      (node (ref "VD35") (pin "3") (pinfunction "3_3") (pintype "passive"))
    )
    (net (code "23") (name "Net-(R23-Pad1)") (class "Default")
      (node (ref "R23") (pin "1") (pinfunction "1_1") (pintype "passive"))
      (node (ref "VD36") (pin "3") (pinfunction "3_3") (pintype "passive"))
    )
    (net (code "24") (name "Net-(R24-Pad1)") (class "Default")
      (node (ref "R24") (pin "1") (pinfunction "1_1") (pintype "passive"))
      (node (ref "VD37") (pin "3") (pinfunction "3_3") (pintype "passive"))
    )
    (net (code "25") (name "Net-(R25-Pad1)") (class "Default")
      (node (ref "R25") (pin "1") (pinfunction "1_1") (pintype "passive"))
      (node (ref "VD38") (pin "3") (pinfunction "3_3") (pintype "passive"))
    )
    (net (code "26") (name "Net-(R26-Pad1)") (class "Default")
      (node (ref "R26") (pin "1") (pinfunction "1_1") (pintype "passive"))
      (node (ref "VD39") (pin "3") (pinfunction "3_3") (pintype "passive"))
    )
    (net (code "27") (name "Net-(R27-Pad1)") (class "Default")
      (node (ref "R27") (pin "1") (pinfunction "1_1") (pintype "passive"))
      (node (ref "VD40") (pin "3") (pinfunction "3_3") (pintype "passive"))
    )
    (net (code "28") (name "Net-(R28-Pad1)") (class "Default")
      (node (ref "R28") (pin "1") (pinfunction "1_1") (pintype "passive"))
      (node (ref "VD41") (pin "3") (pinfunction "3_3") (pintype "passive"))
    )
    (net (code "29") (name "Net-(R29-Pad1)") (class "Default")
      (node (ref "R29") (pin "1") (pinfunction "1_1") (pintype "passive"))
      (node (ref "VD42") (pin "3") (pinfunction "3_3") (pintype "passive"))
    )
    (net (code "30") (name "Net-(R31-Pad1)") (class "Default")
      (node (ref "R31") (pin "1") (pinfunction "1_1") (pintype "passive"))
      (node (ref "VD57") (pin "3") (pinfunction "3_3") (pintype "passive"))
    )
    (net (code "31") (name "Net-(R32-Pad1)") (class "Default")
      (node (ref "R32") (pin "1") (pinfunction "1_1") (pintype "passive"))
      (node (ref "VD58") (pin "3") (pinfunction "3_3") (pintype "passive"))
    )
    (net (code "32") (name "Net-(R33-Pad1)") (class "Default")
      (node (ref "R33") (pin "1") (pinfunction "1_1") (pintype "passive"))
      (node (ref "VD59") (pin "3") (pinfunction "3_3") (pintype "passive"))
    )
    (net (code "33") (name "Net-(R34-Pad1)") (class "Default")
      (node (ref "R34") (pin "1") (pinfunction "1_1") (pintype "passive"))
      (node (ref "VD60") (pin "3") (pinfunction "3_3") (pintype "passive"))
    )
    (net (code "34") (name "Net-(R35-Pad1)") (class "Default")
      (node (ref "R35") (pin "1") (pinfunction "1_1") (pintype "passive"))
      (node (ref "VD61") (pin "3") (pinfunction "3_3") (pintype "passive"))
    )
    (net (code "35") (name "Net-(R36-Pad1)") (class "Default")
      (node (ref "R36") (pin "1") (pinfunction "1_1") (pintype "passive"))
      (node (ref "VD62") (pin "3") (pinfunction "3_3") (pintype "passive"))
    )
    (net (code "36") (name "Net-(R37-Pad1)") (class "Default")
      (node (ref "R37") (pin "1") (pinfunction "1_1") (pintype "passive"))
      (node (ref "VD63") (pin "3") (pinfunction "3_3") (pintype "passive"))
    )
    (net (code "37") (name "Net-(R38-Pad1)") (class "Default")
      (node (ref "R38") (pin "1") (pinfunction "1_1") (pintype "passive"))
      (node (ref "VD64") (pin "3") (pinfunction "3_3") (pintype "passive"))
    )
    (net (code "38") (name "Net-(R39-Pad1)") (class "Default")
      (node (ref "R39") (pin "1") (pinfunction "1_1") (pintype "passive"))
      (node (ref "VD65") (pin "3") (pinfunction "3_3") (pintype "passive"))
    )
    (net (code "39") (name "Net-(R40-Pad1)") (class "Default")
      (node (ref "R40") (pin "1") (pinfunction "1_1") (pintype "passive"))
      (node (ref "VD66") (pin "3") (pinfunction "3_3") (pintype "passive"))
    )
    (net (code "40") (name "Net-(R41-Pad1)") (class "Default")
      (node (ref "R41") (pin "1") (pinfunction "1_1") (pintype "passive"))
      (node (ref "VD67") (pin "3") (pinfunction "3_3") (pintype "passive"))
    )
    (net (code "41") (name "Net-(R42-Pad1)") (class "Default")
      (node (ref "R42") (pin "1") (pinfunction "1_1") (pintype "passive"))
      (node (ref "VD68") (pin "3") (pinfunction "3_3") (pintype "passive"))
    )
    (net (code "42") (name "Net-(R43-Pad1)") (class "Default")
      (node (ref "R43") (pin "1") (pinfunction "1_1") (pintype "passive"))
      (node (ref "VD69") (pin "3") (pinfunction "3_3") (pintype "passive"))
    )
    (net (code "43") (name "Net-(R44-Pad1)") (class "Default")
      (node (ref "R44") (pin "1") (pinfunction "1_1") (pintype "passive"))
      (node (ref "VD70") (pin "3") (pinfunction "3_3") (pintype "passive"))
    )
    (net (code "44") (name "Net-(R46-Pad1)") (class "Default")
      (node (ref "R46") (pin "1") (pinfunction "1_1") (pintype "passive"))
      (node (ref "VD85") (pin "3") (pinfunction "3_3") (pintype "passive"))
    )
    (net (code "45") (name "Net-(R47-Pad1)") (class "Default")
      (node (ref "R47") (pin "1") (pinfunction "1_1") (pintype "passive"))
      (node (ref "VD86") (pin "3") (pinfunction "3_3") (pintype "passive"))
    )
    (net (code "46") (name "Net-(R48-Pad1)") (class "Default")
      (node (ref "R48") (pin "1") (pinfunction "1_1") (pintype "passive"))
      (node (ref "VD87") (pin "3") (pinfunction "3_3") (pintype "passive"))
    )
    (net (code "47") (name "Net-(R49-Pad1)") (class "Default")
      (node (ref "R49") (pin "1") (pinfunction "1_1") (pintype "passive"))
      (node (ref "VD88") (pin "3") (pinfunction "3_3") (pintype "passive"))
    )
    (net (code "48") (name "Net-(R50-Pad1)") (class "Default")
      (node (ref "R50") (pin "1") (pinfunction "1_1") (pintype "passive"))
      (node (ref "VD89") (pin "3") (pinfunction "3_3") (pintype "passive"))
    )
    (net (code "49") (name "Net-(R51-Pad1)") (class "Default")
      (node (ref "R51") (pin "1") (pinfunction "1_1") (pintype "passive"))
      (node (ref "VD90") (pin "3") (pinfunction "3_3") (pintype "passive"))
    )
    (net (code "50") (name "Net-(R52-Pad1)") (class "Default")
      (node (ref "R52") (pin "1") (pinfunction "1_1") (pintype "passive"))
      (node (ref "VD91") (pin "3") (pinfunction "3_3") (pintype "passive"))
    )
    (net (code "51") (name "Net-(R53-Pad1)") (class "Default")
      (node (ref "R53") (pin "1") (pinfunction "1_1") (pintype "passive"))
      (node (ref "VD92") (pin "3") (pinfunction "3_3") (pintype "passive"))
    )
    (net (code "52") (name "Net-(R54-Pad1)") (class "Default")
      (node (ref "R54") (pin "1") (pinfunction "1_1") (pintype "passive"))
      (node (ref "VD93") (pin "3") (pinfunction "3_3") (pintype "passive"))
    )
    (net (code "53") (name "Net-(R55-Pad1)") (class "Default")
      (node (ref "R55") (pin "1") (pinfunction "1_1") (pintype "passive"))
      (node (ref "VD94") (pin "3") (pinfunction "3_3") (pintype "passive"))
    )
    (net (code "54") (name "Net-(R56-Pad1)") (class "Default")
      (node (ref "R56") (pin "1") (pinfunction "1_1") (pintype "passive"))
      (node (ref "VD95") (pin "3") (pinfunction "3_3") (pintype "passive"))
    )
    (net (code "55") (name "Net-(R57-Pad1)") (class "Default")
      (node (ref "R57") (pin "1") (pinfunction "1_1") (pintype "passive"))
      (node (ref "VD96") (pin "3") (pinfunction "3_3") (pintype "passive"))
    )
    (net (code "56") (name "Net-(R58-Pad1)") (class "Default")
      (node (ref "R58") (pin "1") (pinfunction "1_1") (pintype "passive"))
      (node (ref "VD97") (pin "3") (pinfunction "3_3") (pintype "passive"))
    )
    (net (code "57") (name "Net-(R59-Pad1)") (class "Default")
      (node (ref "R59") (pin "1") (pinfunction "1_1") (pintype "passive"))
      (node (ref "VD98") (pin "3") (pinfunction "3_3") (pintype "passive"))
    )
    (net (code "58") (name "Net-(R61-Pad1)") (class "Default")
      (node (ref "R61") (pin "1") (pinfunction "1_1") (pintype "passive"))
      (node (ref "VD113") (pin "3") (pinfunction "3_3") (pintype "passive"))
    )
    (net (code "59") (name "Net-(R62-Pad1)") (class "Default")
      (node (ref "R62") (pin "1") (pinfunction "1_1") (pintype "passive"))
      (node (ref "VD114") (pin "3") (pinfunction "3_3") (pintype "passive"))
    )
    (net (code "60") (name "Net-(R63-Pad1)") (class "Default")
      (node (ref "R63") (pin "1") (pinfunction "1_1") (pintype "passive"))
      (node (ref "VD115") (pin "3") (pinfunction "3_3") (pintype "passive"))
    )
    (net (code "61") (name "Net-(R64-Pad1)") (class "Default")
      (node (ref "R64") (pin "1") (pinfunction "1_1") (pintype "passive"))
      (node (ref "VD116") (pin "3") (pinfunction "3_3") (pintype "passive"))
    )
    (net (code "62") (name "Net-(R65-Pad1)") (class "Default")
      (node (ref "R65") (pin "1") (pinfunction "1_1") (pintype "passive"))
      (node (ref "VD117") (pin "3") (pinfunction "3_3") (pintype "passive"))
    )
    (net (code "63") (name "Net-(R66-Pad1)") (class "Default")
      (node (ref "R66") (pin "1") (pinfunction "1_1") (pintype "passive"))
      (node (ref "VD118") (pin "3") (pinfunction "3_3") (pintype "passive"))
    )
    (net (code "64") (name "Net-(R67-Pad1)") (class "Default")
      (node (ref "R67") (pin "1") (pinfunction "1_1") (pintype "passive"))
      (node (ref "VD119") (pin "3") (pinfunction "3_3") (pintype "passive"))
    )
    (net (code "65") (name "Net-(R68-Pad1)") (class "Default")
      (node (ref "R68") (pin "1") (pinfunction "1_1") (pintype "passive"))
      (node (ref "VD120") (pin "3") (pinfunction "3_3") (pintype "passive"))
    )
    (net (code "66") (name "Net-(R69-Pad1)") (class "Default")
      (node (ref "R69") (pin "1") (pinfunction "1_1") (pintype "passive"))
      (node (ref "VD121") (pin "3") (pinfunction "3_3") (pintype "passive"))
    )
    (net (code "67") (name "Net-(R70-Pad1)") (class "Default")
      (node (ref "R70") (pin "1") (pinfunction "1_1") (pintype "passive"))
      (node (ref "VD122") (pin "3") (pinfunction "3_3") (pintype "passive"))
    )
    (net (code "68") (name "Net-(R71-Pad1)") (class "Default")
      (node (ref "R71") (pin "1") (pinfunction "1_1") (pintype "passive"))
      (node (ref "VD123") (pin "3") (pinfunction "3_3") (pintype "passive"))
    )
    (net (code "69") (name "Net-(R72-Pad1)") (class "Default")
      (node (ref "R72") (pin "1") (pinfunction "1_1") (pintype "passive"))
      (node (ref "VD124") (pin "3") (pinfunction "3_3") (pintype "passive"))
    )
    (net (code "70") (name "Net-(R73-Pad1)") (class "Default")
      (node (ref "R73") (pin "1") (pinfunction "1_1") (pintype "passive"))
      (node (ref "VD125") (pin "3") (pinfunction "3_3") (pintype "passive"))
    )
    (net (code "71") (name "Net-(R74-Pad1)") (class "Default")
      (node (ref "R74") (pin "1") (pinfunction "1_1") (pintype "passive"))
      (node (ref "VD126") (pin "3") (pinfunction "3_3") (pintype "passive"))
    )
    (net (code "72") (name "Net-(R76-Pad1)") (class "Default")
      (node (ref "R76") (pin "1") (pinfunction "1_1") (pintype "passive"))
      (node (ref "VD141") (pin "3") (pinfunction "3_3") (pintype "passive"))
    )
    (net (code "73") (name "Net-(R77-Pad1)") (class "Default")
      (node (ref "R77") (pin "1") (pinfunction "1_1") (pintype "passive"))
      (node (ref "VD142") (pin "3") (pinfunction "3_3") (pintype "passive"))
    )
    (net (code "74") (name "Net-(R78-Pad1)") (class "Default")
      (node (ref "R78") (pin "1") (pinfunction "1_1") (pintype "passive"))
      (node (ref "VD143") (pin "3") (pinfunction "3_3") (pintype "passive"))
    )
    (net (code "75") (name "Net-(R79-Pad1)") (class "Default")
      (node (ref "R79") (pin "1") (pinfunction "1_1") (pintype "passive"))
      (node (ref "VD144") (pin "3") (pinfunction "3_3") (pintype "passive"))
    )
    (net (code "76") (name "Net-(R80-Pad1)") (class "Default")
      (node (ref "R80") (pin "1") (pinfunction "1_1") (pintype "passive"))
      (node (ref "VD145") (pin "3") (pinfunction "3_3") (pintype "passive"))
    )
    (net (code "77") (name "Net-(R81-Pad1)") (class "Default")
      (node (ref "R81") (pin "1") (pinfunction "1_1") (pintype "passive"))
      (node (ref "VD146") (pin "3") (pinfunction "3_3") (pintype "passive"))
    )
    (net (code "78") (name "Net-(R82-Pad1)") (class "Default")
      (node (ref "R82") (pin "1") (pinfunction "1_1") (pintype "passive"))
      (node (ref "VD147") (pin "3") (pinfunction "3_3") (pintype "passive"))
    )
    (net (code "79") (name "Net-(R83-Pad1)") (class "Default")
      (node (ref "R83") (pin "1") (pinfunction "1_1") (pintype "passive"))
      (node (ref "VD148") (pin "3") (pinfunction "3_3") (pintype "passive"))
    )
    (net (code "80") (name "Net-(R84-Pad1)") (class "Default")
      (node (ref "R84") (pin "1") (pinfunction "1_1") (pintype "passive"))
      (node (ref "VD149") (pin "3") (pinfunction "3_3") (pintype "passive"))
    )
    (net (code "81") (name "Net-(R85-Pad1)") (class "Default")
      (node (ref "R85") (pin "1") (pinfunction "1_1") (pintype "passive"))
      (node (ref "VD150") (pin "3") (pinfunction "3_3") (pintype "passive"))
    )
    (net (code "82") (name "Net-(R86-Pad1)") (class "Default")
      (node (ref "R86") (pin "1") (pinfunction "1_1") (pintype "passive"))
      (node (ref "VD151") (pin "3") (pinfunction "3_3") (pintype "passive"))
    )
    (net (code "83") (name "Net-(R87-Pad1)") (class "Default")
      (node (ref "R87") (pin "1") (pinfunction "1_1") (pintype "passive"))
      (node (ref "VD152") (pin "3") (pinfunction "3_3") (pintype "passive"))
    )
    (net (code "84") (name "Net-(R88-Pad1)") (class "Default")
      (node (ref "R88") (pin "1") (pinfunction "1_1") (pintype "passive"))
      (node (ref "VD153") (pin "3") (pinfunction "3_3") (pintype "passive"))
    )
    (net (code "85") (name "Net-(R89-Pad1)") (class "Default")
      (node (ref "R89") (pin "1") (pinfunction "1_1") (pintype "passive"))
      (node (ref "VD154") (pin "3") (pinfunction "3_3") (pintype "passive"))
    )
    (net (code "86") (name "Net-(SB1-Pad2)") (class "Default")
      (node (ref "SB1") (pin "2") (pinfunction "2_2") (pintype "passive"))
      (node (ref "SB15") (pin "2") (pinfunction "2_2") (pintype "passive"))
      (node (ref "SB29") (pin "2") (pinfunction "2_2") (pintype "passive"))
      (node (ref "SB43") (pin "2") (pinfunction "2_2") (pintype "passive"))
      (node (ref "SB57") (pin "2") (pinfunction "2_2") (pintype "passive"))
      (node (ref "SB71") (pin "2") (pinfunction "2_2") (pintype "passive"))
      (node (ref "X3") (pin "1") (pinfunction "1_1") (pintype "passive"))
    )
    (net (code "87") (name "Net-(SB10-Pad2)") (class "Default")
      (node (ref "SB10") (pin "2") (pinfunction "2_2") (pintype "passive"))
      (node (ref "SB24") (pin "2") (pinfunction "2_2") (pintype "passive"))
      (node (ref "SB38") (pin "2") (pinfunction "2_2") (pintype "passive"))
      (node (ref "SB52") (pin "2") (pinfunction "2_2") (pintype "passive"))
      (node (ref "SB66") (pin "2") (pinfunction "2_2") (pintype "passive"))
      (node (ref "SB80") (pin "2") (pinfunction "2_2") (pintype "passive"))
      (node (ref "X3") (pin "10") (pinfunction "10_10") (pintype "passive"))
    )
    (net (code "88") (name "Net-(SB11-Pad2)") (class "Default")
      (node (ref "SB11") (pin "2") (pinfunction "2_2") (pintype "passive"))
      (node (ref "SB25") (pin "2") (pinfunction "2_2") (pintype "passive"))
      (node (ref "SB39") (pin "2") (pinfunction "2_2") (pintype "passive"))
      (node (ref "SB53") (pin "2") (pinfunction "2_2") (pintype "passive"))
      (node (ref "SB67") (pin "2") (pinfunction "2_2") (pintype "passive"))
      (node (ref "SB81") (pin "2") (pinfunction "2_2") (pintype "passive"))
      (node (ref "X3") (pin "11") (pinfunction "11_11") (pintype "passive"))
    )
    (net (code "89") (name "Net-(SB12-Pad2)") (class "Default")
      (node (ref "SB12") (pin "2") (pinfunction "2_2") (pintype "passive"))
      (node (ref "SB26") (pin "2") (pinfunction "2_2") (pintype "passive"))
      (node (ref "SB40") (pin "2") (pinfunction "2_2") (pintype "passive"))
      (node (ref "SB54") (pin "2") (pinfunction "2_2") (pintype "passive"))
      (node (ref "SB68") (pin "2") (pinfunction "2_2") (pintype "passive"))
      (node (ref "SB82") (pin "2") (pinfunction "2_2") (pintype "passive"))
      (node (ref "X3") (pin "12") (pinfunction "12_12") (pintype "passive"))
    )
    (net (code "90") (name "Net-(SB13-Pad2)") (class "Default")
      (node (ref "SB13") (pin "2") (pinfunction "2_2") (pintype "passive"))
      (node (ref "SB27") (pin "2") (pinfunction "2_2") (pintype "passive"))
      (node (ref "SB41") (pin "2") (pinfunction "2_2") (pintype "passive"))
      (node (ref "SB55") (pin "2") (pinfunction "2_2") (pintype "passive"))
      (node (ref "SB69") (pin "2") (pinfunction "2_2") (pintype "passive"))
      (node (ref "SB83") (pin "2") (pinfunction "2_2") (pintype "passive"))
      (node (ref "X3") (pin "13") (pinfunction "13_13") (pintype "passive"))
    )
    (net (code "91") (name "Net-(SB14-Pad2)") (class "Default")
      (node (ref "SB14") (pin "2") (pinfunction "2_2") (pintype "passive"))
      (node (ref "SB28") (pin "2") (pinfunction "2_2") (pintype "passive"))
      (node (ref "SB42") (pin "2") (pinfunction "2_2") (pintype "passive"))
      (node (ref "SB56") (pin "2") (pinfunction "2_2") (pintype "passive"))
      (node (ref "SB70") (pin "2") (pinfunction "2_2") (pintype "passive"))
      (node (ref "SB84") (pin "2") (pinfunction "2_2") (pintype "passive"))
      (node (ref "X3") (pin "14") (pinfunction "14_14") (pintype "passive"))
    )
    (net (code "92") (name "Net-(SB16-Pad2)") (class "Default")
      (node (ref "SB16") (pin "2") (pinfunction "2_2") (pintype "passive"))
      (node (ref "SB2") (pin "2") (pinfunction "2_2") (pintype "passive"))
      (node (ref "SB30") (pin "2") (pinfunction "2_2") (pintype "passive"))
      (node (ref "SB44") (pin "2") (pinfunction "2_2") (pintype "passive"))
      (node (ref "SB58") (pin "2") (pinfunction "2_2") (pintype "passive"))
      (node (ref "SB72") (pin "2") (pinfunction "2_2") (pintype "passive"))
      (node (ref "X3") (pin "2") (pinfunction "2_2") (pintype "passive"))
    )
    (net (code "93") (name "Net-(SB17-Pad2)") (class "Default")
      (node (ref "SB17") (pin "2") (pinfunction "2_2") (pintype "passive"))
      (node (ref "SB3") (pin "2") (pinfunction "2_2") (pintype "passive"))
      (node (ref "SB31") (pin "2") (pinfunction "2_2") (pintype "passive"))
      (node (ref "SB45") (pin "2") (pinfunction "2_2") (pintype "passive"))
      (node (ref "SB59") (pin "2") (pinfunction "2_2") (pintype "passive"))
      (node (ref "SB73") (pin "2") (pinfunction "2_2") (pintype "passive"))
      (node (ref "X3") (pin "3") (pinfunction "3_3") (pintype "passive"))
    )
    (net (code "94") (name "Net-(SB18-Pad2)") (class "Default")
      (node (ref "SB18") (pin "2") (pinfunction "2_2") (pintype "passive"))
      (node (ref "SB32") (pin "2") (pinfunction "2_2") (pintype "passive"))
      (node (ref "SB4") (pin "2") (pinfunction "2_2") (pintype "passive"))
      (node (ref "SB46") (pin "2") (pinfunction "2_2") (pintype "passive"))
      (node (ref "SB60") (pin "2") (pinfunction "2_2") (pintype "passive"))
      (node (ref "SB74") (pin "2") (pinfunction "2_2") (pintype "passive"))
      (node (ref "X3") (pin "4") (pinfunction "4_4") (pintype "passive"))
    )
    (net (code "95") (name "Net-(SB19-Pad2)") (class "Default")
      (node (ref "SB19") (pin "2") (pinfunction "2_2") (pintype "passive"))
      (node (ref "SB33") (pin "2") (pinfunction "2_2") (pintype "passive"))
      (node (ref "SB47") (pin "2") (pinfunction "2_2") (pintype "passive"))
      (node (ref "SB5") (pin "2") (pinfunction "2_2") (pintype "passive"))
      (node (ref "SB61") (pin "2") (pinfunction "2_2") (pintype "passive"))
      (node (ref "SB75") (pin "2") (pinfunction "2_2") (pintype "passive"))
      (node (ref "X3") (pin "5") (pinfunction "5_5") (pintype "passive"))
    )
    (net (code "96") (name "Net-(SB20-Pad2)") (class "Default")
      (node (ref "SB20") (pin "2") (pinfunction "2_2") (pintype "passive"))
      (node (ref "SB34") (pin "2") (pinfunction "2_2") (pintype "passive"))
      (node (ref "SB48") (pin "2") (pinfunction "2_2") (pintype "passive"))
      (node (ref "SB6") (pin "2") (pinfunction "2_2") (pintype "passive"))
      (node (ref "SB62") (pin "2") (pinfunction "2_2") (pintype "passive"))
      (node (ref "SB76") (pin "2") (pinfunction "2_2") (pintype "passive"))
      (node (ref "X3") (pin "6") (pinfunction "6_6") (pintype "passive"))
    )
    (net (code "97") (name "Net-(SB21-Pad2)") (class "Default")
      (node (ref "SB21") (pin "2") (pinfunction "2_2") (pintype "passive"))
      (node (ref "SB35") (pin "2") (pinfunction "2_2") (pintype "passive"))
      (node (ref "SB49") (pin "2") (pinfunction "2_2") (pintype "passive"))
      (node (ref "SB63") (pin "2") (pinfunction "2_2") (pintype "passive"))
      (node (ref "SB7") (pin "2") (pinfunction "2_2") (pintype "passive"))
      (node (ref "SB77") (pin "2") (pinfunction "2_2") (pintype "passive"))
      (node (ref "X3") (pin "7") (pinfunction "7_7") (pintype "passive"))
    )
    (net (code "98") (name "Net-(SB22-Pad2)") (class "Default")
      (node (ref "SB22") (pin "2") (pinfunction "2_2") (pintype "passive"))
      (node (ref "SB36") (pin "2") (pinfunction "2_2") (pintype "passive"))
      (node (ref "SB50") (pin "2") (pinfunction "2_2") (pintype "passive"))
      (node (ref "SB64") (pin "2") (pinfunction "2_2") (pintype "passive"))
      (node (ref "SB78") (pin "2") (pinfunction "2_2") (pintype "passive"))
      (node (ref "SB8") (pin "2") (pinfunction "2_2") (pintype "passive"))
      (node (ref "X3") (pin "8") (pinfunction "8_8") (pintype "passive"))
    )
    (net (code "99") (name "Net-(SB23-Pad2)") (class "Default")
      (node (ref "SB23") (pin "2") (pinfunction "2_2") (pintype "passive"))
      (node (ref "SB37") (pin "2") (pinfunction "2_2") (pintype "passive"))
      (node (ref "SB51") (pin "2") (pinfunction "2_2") (pintype "passive"))
      (node (ref "SB65") (pin "2") (pinfunction "2_2") (pintype "passive"))
      (node (ref "SB79") (pin "2") (pinfunction "2_2") (pintype "passive"))
      (node (ref "SB9") (pin "2") (pinfunction "2_2") (pintype "passive"))
      (node (ref "X3") (pin "9") (pinfunction "9_9") (pintype "passive"))
    )
    (net (code "100") (name "Net-(VD1-Pad4)") (class "Default")
      (node (ref "VD1") (pin "4") (pinfunction "4_4") (pintype "passive"))
      (node (ref "VD10") (pin "4") (pinfunction "4_4") (pintype "passive"))
      (node (ref "VD11") (pin "4") (pinfunction "4_4") (pintype "passive"))
      (node (ref "VD113") (pin "4") (pinfunction "4_4") (pintype "passive"))
      (node (ref "VD114") (pin "4") (pinfunction "4_4") (pintype "passive"))
      (node (ref "VD115") (pin "4") (pinfunction "4_4") (pintype "passive"))
      (node (ref "VD116") (pin "4") (pinfunction "4_4") (pintype "passive"))
      (node (ref "VD117") (pin "4") (pinfunction "4_4") (pintype "passive"))
      (node (ref "VD118") (pin "4") (pinfunction "4_4") (pintype "passive"))
      (node (ref "VD119") (pin "4") (pinfunction "4_4") (pintype "passive"))
      (node (ref "VD12") (pin "4") (pinfunction "4_4") (pintype "passive"))
      (node (ref "VD120") (pin "4") (pinfunction "4_4") (pintype "passive"))
      (node (ref "VD121") (pin "4") (pinfunction "4_4") (pintype "passive"))
      (node (ref "VD122") (pin "4") (pinfunction "4_4") (pintype "passive"))
      (node (ref "VD123") (pin "4") (pinfunction "4_4") (pintype "passive"))
      (node (ref "VD124") (pin "4") (pinfunction "4_4") (pintype "passive"))
      (node (ref "VD125") (pin "4") (pinfunction "4_4") (pintype "passive"))
      (node (ref "VD126") (pin "4") (pinfunction "4_4") (pintype "passive"))
      (node (ref "VD13") (pin "4") (pinfunction "4_4") (pintype "passive"))
      (node (ref "VD14") (pin "4") (pinfunction "4_4") (pintype "passive"))
      (node (ref "VD141") (pin "4") (pinfunction "4_4") (pintype "passive"))
      (node (ref "VD142") (pin "4") (pinfunction "4_4") (pintype "passive"))
      (node (ref "VD143") (pin "4") (pinfunction "4_4") (pintype "passive"))
      (node (ref "VD144") (pin "4") (pinfunction "4_4") (pintype "passive"))
      (node (ref "VD145") (pin "4") (pinfunction "4_4") (pintype "passive"))
      (node (ref "VD146") (pin "4") (pinfunction "4_4") (pintype "passive"))
      (node (ref "VD147") (pin "4") (pinfunction "4_4") (pintype "passive"))
      (node (ref "VD148") (pin "4") (pinfunction "4_4") (pintype "passive"))
      (node (ref "VD149") (pin "4") (pinfunction "4_4") (pintype "passive"))
      (node (ref "VD150") (pin "4") (pinfunction "4_4") (pintype "passive"))
      (node (ref "VD151") (pin "4") (pinfunction "4_4") (pintype "passive"))
      (node (ref "VD152") (pin "4") (pinfunction "4_4") (pintype "passive"))
      (node (ref "VD153") (pin "4") (pinfunction "4_4") (pintype "passive"))
      (node (ref "VD154") (pin "4") (pinfunction "4_4") (pintype "passive"))
      (node (ref "VD2") (pin "4") (pinfunction "4_4") (pintype "passive"))
      (node (ref "VD29") (pin "4") (pinfunction "4_4") (pintype "passive"))
      (node (ref "VD3") (pin "4") (pinfunction "4_4") (pintype "passive"))
      (node (ref "VD30") (pin "4") (pinfunction "4_4") (pintype "passive"))
      (node (ref "VD31") (pin "4") (pinfunction "4_4") (pintype "passive"))
      (node (ref "VD32") (pin "4") (pinfunction "4_4") (pintype "passive"))
      (node (ref "VD33") (pin "4") (pinfunction "4_4") (pintype "passive"))
      (node (ref "VD34") (pin "4") (pinfunction "4_4") (pintype "passive"))
      (node (ref "VD35") (pin "4") (pinfunction "4_4") (pintype "passive"))
      (node (ref "VD36") (pin "4") (pinfunction "4_4") (pintype "passive"))
      (node (ref "VD37") (pin "4") (pinfunction "4_4") (pintype "passive"))
      (node (ref "VD38") (pin "4") (pinfunction "4_4") (pintype "passive"))
      (node (ref "VD39") (pin "4") (pinfunction "4_4") (pintype "passive"))
      (node (ref "VD4") (pin "4") (pinfunction "4_4") (pintype "passive"))
      (node (ref "VD40") (pin "4") (pinfunction "4_4") (pintype "passive"))
      (node (ref "VD41") (pin "4") (pinfunction "4_4") (pintype "passive"))
      (node (ref "VD42") (pin "4") (pinfunction "4_4") (pintype "passive"))
      (node (ref "VD5") (pin "4") (pinfunction "4_4") (pintype "passive"))
      (node (ref "VD57") (pin "4") (pinfunction "4_4") (pintype "passive"))
      (node (ref "VD58") (pin "4") (pinfunction "4_4") (pintype "passive"))
      (node (ref "VD59") (pin "4") (pinfunction "4_4") (pintype "passive"))
      (node (ref "VD6") (pin "4") (pinfunction "4_4") (pintype "passive"))
      (node (ref "VD60") (pin "4") (pinfunction "4_4") (pintype "passive"))
      (node (ref "VD61") (pin "4") (pinfunction "4_4") (pintype "passive"))
      (node (ref "VD62") (pin "4") (pinfunction "4_4") (pintype "passive"))
      (node (ref "VD63") (pin "4") (pinfunction "4_4") (pintype "passive"))
      (node (ref "VD64") (pin "4") (pinfunction "4_4") (pintype "passive"))
      (node (ref "VD65") (pin "4") (pinfunction "4_4") (pintype "passive"))
      (node (ref "VD66") (pin "4") (pinfunction "4_4") (pintype "passive"))
      (node (ref "VD67") (pin "4") (pinfunction "4_4") (pintype "passive"))
      (node (ref "VD68") (pin "4") (pinfunction "4_4") (pintype "passive"))
      (node (ref "VD69") (pin "4") (pinfunction "4_4") (pintype "passive"))
      (node (ref "VD7") (pin "4") (pinfunction "4_4") (pintype "passive"))
      (node (ref "VD70") (pin "4") (pinfunction "4_4") (pintype "passive"))
      (node (ref "VD8") (pin "4") (pinfunction "4_4") (pintype "passive"))
      (node (ref "VD85") (pin "4") (pinfunction "4_4") (pintype "passive"))
      (node (ref "VD86") (pin "4") (pinfunction "4_4") (pintype "passive"))
      (node (ref "VD87") (pin "4") (pinfunction "4_4") (pintype "passive"))
      (node (ref "VD88") (pin "4") (pinfunction "4_4") (pintype "passive"))
      (node (ref "VD89") (pin "4") (pinfunction "4_4") (pintype "passive"))
      (node (ref "VD9") (pin "4") (pinfunction "4_4") (pintype "passive"))
      (node (ref "VD90") (pin "4") (pinfunction "4_4") (pintype "passive"))
      (node (ref "VD91") (pin "4") (pinfunction "4_4") (pintype "passive"))
      (node (ref "VD92") (pin "4") (pinfunction "4_4") (pintype "passive"))
      (node (ref "VD93") (pin "4") (pinfunction "4_4") (pintype "passive"))
      (node (ref "VD94") (pin "4") (pinfunction "4_4") (pintype "passive"))
      (node (ref "VD95") (pin "4") (pinfunction "4_4") (pintype "passive"))
      (node (ref "VD96") (pin "4") (pinfunction "4_4") (pintype "passive"))
      (node (ref "VD97") (pin "4") (pinfunction "4_4") (pintype "passive"))
      (node (ref "VD98") (pin "4") (pinfunction "4_4") (pintype "passive"))
      (node (ref "X1") (pin "1") (pinfunction "1_1") (pintype "passive"))
    )
    (net (code "101") (name "Net-(VD15-A)") (class "Default")
      (node (ref "R15") (pin "2") (pinfunction "2_2") (pintype "passive"))
      (node (ref "VD15") (pin "1") (pinfunction "A_1") (pintype "passive"))
      (node (ref "VD16") (pin "1") (pinfunction "A_1") (pintype "passive"))
      (node (ref "VD17") (pin "1") (pinfunction "A_1") (pintype "passive"))
      (node (ref "VD18") (pin "1") (pinfunction "A_1") (pintype "passive"))
      (node (ref "VD19") (pin "1") (pinfunction "A_1") (pintype "passive"))
      (node (ref "VD20") (pin "1") (pinfunction "A_1") (pintype "passive"))
      (node (ref "VD21") (pin "1") (pinfunction "A_1") (pintype "passive"))
      (node (ref "VD22") (pin "1") (pinfunction "A_1") (pintype "passive"))
      (node (ref "VD23") (pin "1") (pinfunction "A_1") (pintype "passive"))
      (node (ref "VD24") (pin "1") (pinfunction "A_1") (pintype "passive"))
      (node (ref "VD25") (pin "1") (pinfunction "A_1") (pintype "passive"))
      (node (ref "VD26") (pin "1") (pinfunction "A_1") (pintype "passive"))
      (node (ref "VD27") (pin "1") (pinfunction "A_1") (pintype "passive"))
      (node (ref "VD28") (pin "1") (pinfunction "A_1") (pintype "passive"))
      (node (ref "X2") (pin "1") (pinfunction "1_1") (pintype "passive"))
    )
    (net (code "102") (name "Net-(VD15-C)") (class "Default")
      (node (ref "SB1") (pin "1") (pinfunction "1_1") (pintype "passive"))
      (node (ref "VD15") (pin "2") (pinfunction "C_2") (pintype "passive"))
    )
    (net (code "103") (name "Net-(VD16-C)") (class "Default")
      (node (ref "SB2") (pin "1") (pinfunction "1_1") (pintype "passive"))
      (node (ref "VD16") (pin "2") (pinfunction "C_2") (pintype "passive"))
    )
    (net (code "104") (name "Net-(VD17-C)") (class "Default")
      (node (ref "SB3") (pin "1") (pinfunction "1_1") (pintype "passive"))
      (node (ref "VD17") (pin "2") (pinfunction "C_2") (pintype "passive"))
    )
    (net (code "105") (name "Net-(VD18-C)") (class "Default")
      (node (ref "SB4") (pin "1") (pinfunction "1_1") (pintype "passive"))
      (node (ref "VD18") (pin "2") (pinfunction "C_2") (pintype "passive"))
    )
    (net (code "106") (name "Net-(VD19-C)") (class "Default")
      (node (ref "SB5") (pin "1") (pinfunction "1_1") (pintype "passive"))
      (node (ref "VD19") (pin "2") (pinfunction "C_2") (pintype "passive"))
    )
    (net (code "107") (name "Net-(VD20-C)") (class "Default")
      (node (ref "SB6") (pin "1") (pinfunction "1_1") (pintype "passive"))
      (node (ref "VD20") (pin "2") (pinfunction "C_2") (pintype "passive"))
    )
    (net (code "108") (name "Net-(VD21-C)") (class "Default")
      (node (ref "SB7") (pin "1") (pinfunction "1_1") (pintype "passive"))
      (node (ref "VD21") (pin "2") (pinfunction "C_2") (pintype "passive"))
    )
    (net (code "109") (name "Net-(VD22-C)") (class "Default")
      (node (ref "SB8") (pin "1") (pinfunction "1_1") (pintype "passive"))
      (node (ref "VD22") (pin "2") (pinfunction "C_2") (pintype "passive"))
    )
    (net (code "110") (name "Net-(VD23-C)") (class "Default")
      (node (ref "SB9") (pin "1") (pinfunction "1_1") (pintype "passive"))
      (node (ref "VD23") (pin "2") (pinfunction "C_2") (pintype "passive"))
    )
    (net (code "111") (name "Net-(VD24-C)") (class "Default")
      (node (ref "SB10") (pin "1") (pinfunction "1_1") (pintype "passive"))
      (node (ref "VD24") (pin "2") (pinfunction "C_2") (pintype "passive"))
    )
    (net (code "112") (name "Net-(VD25-C)") (class "Default")
      (node (ref "SB11") (pin "1") (pinfunction "1_1") (pintype "passive"))
      (node (ref "VD25") (pin "2") (pinfunction "C_2") (pintype "passive"))
    )
    (net (code "113") (name "Net-(VD26-C)") (class "Default")
      (node (ref "SB12") (pin "1") (pinfunction "1_1") (pintype "passive"))
      (node (ref "VD26") (pin "2") (pinfunction "C_2") (pintype "passive"))
    )
    (net (code "114") (name "Net-(VD27-C)") (class "Default")
      (node (ref "SB13") (pin "1") (pinfunction "1_1") (pintype "passive"))
      (node (ref "VD27") (pin "2") (pinfunction "C_2") (pintype "passive"))
    )
    (net (code "115") (name "Net-(VD28-C)") (class "Default")
      (node (ref "SB14") (pin "1") (pinfunction "1_1") (pintype "passive"))
      (node (ref "VD28") (pin "2") (pinfunction "C_2") (pintype "passive"))
    )
    (net (code "116") (name "Net-(VD43-A)") (class "Default")
      (node (ref "R30") (pin "2") (pinfunction "2_2") (pintype "passive"))
      (node (ref "VD43") (pin "1") (pinfunction "A_1") (pintype "passive"))
      (node (ref "VD44") (pin "1") (pinfunction "A_1") (pintype "passive"))
      (node (ref "VD45") (pin "1") (pinfunction "A_1") (pintype "passive"))
      (node (ref "VD46") (pin "1") (pinfunction "A_1") (pintype "passive"))
      (node (ref "VD47") (pin "1") (pinfunction "A_1") (pintype "passive"))
      (node (ref "VD48") (pin "1") (pinfunction "A_1") (pintype "passive"))
      (node (ref "VD49") (pin "1") (pinfunction "A_1") (pintype "passive"))
      (node (ref "VD50") (pin "1") (pinfunction "A_1") (pintype "passive"))
      (node (ref "VD51") (pin "1") (pinfunction "A_1") (pintype "passive"))
      (node (ref "VD52") (pin "1") (pinfunction "A_1") (pintype "passive"))
      (node (ref "VD53") (pin "1") (pinfunction "A_1") (pintype "passive"))
      (node (ref "VD54") (pin "1") (pinfunction "A_1") (pintype "passive"))
      (node (ref "VD55") (pin "1") (pinfunction "A_1") (pintype "passive"))
      (node (ref "VD56") (pin "1") (pinfunction "A_1") (pintype "passive"))
      (node (ref "X2") (pin "2") (pinfunction "2_2") (pintype "passive"))
    )
    (net (code "117") (name "Net-(VD43-C)") (class "Default")
      (node (ref "SB15") (pin "1") (pinfunction "1_1") (pintype "passive"))
      (node (ref "VD43") (pin "2") (pinfunction "C_2") (pintype "passive"))
    )
    (net (code "118") (name "Net-(VD44-C)") (class "Default")
      (node (ref "SB16") (pin "1") (pinfunction "1_1") (pintype "passive"))
      (node (ref "VD44") (pin "2") (pinfunction "C_2") (pintype "passive"))
    )
    (net (code "119") (name "Net-(VD45-C)") (class "Default")
      (node (ref "SB17") (pin "1") (pinfunction "1_1") (pintype "passive"))
      (node (ref "VD45") (pin "2") (pinfunction "C_2") (pintype "passive"))
    )
    (net (code "120") (name "Net-(VD46-C)") (class "Default")
      (node (ref "SB18") (pin "1") (pinfunction "1_1") (pintype "passive"))
      (node (ref "VD46") (pin "2") (pinfunction "C_2") (pintype "passive"))
    )
    (net (code "121") (name "Net-(VD47-C)") (class "Default")
      (node (ref "SB19") (pin "1") (pinfunction "1_1") (pintype "passive"))
      (node (ref "VD47") (pin "2") (pinfunction "C_2") (pintype "passive"))
    )
    (net (code "122") (name "Net-(VD48-C)") (class "Default")
      (node (ref "SB20") (pin "1") (pinfunction "1_1") (pintype "passive"))
      (node (ref "VD48") (pin "2") (pinfunction "C_2") (pintype "passive"))
    )
    (net (code "123") (name "Net-(VD49-C)") (class "Default")
      (node (ref "SB21") (pin "1") (pinfunction "1_1") (pintype "passive"))
      (node (ref "VD49") (pin "2") (pinfunction "C_2") (pintype "passive"))
    )
    (net (code "124") (name "Net-(VD50-C)") (class "Default")
      (node (ref "SB22") (pin "1") (pinfunction "1_1") (pintype "passive"))
      (node (ref "VD50") (pin "2") (pinfunction "C_2") (pintype "passive"))
    )
    (net (code "125") (name "Net-(VD51-C)") (class "Default")
      (node (ref "SB23") (pin "1") (pinfunction "1_1") (pintype "passive"))
      (node (ref "VD51") (pin "2") (pinfunction "C_2") (pintype "passive"))
    )
    (net (code "126") (name "Net-(VD52-C)") (class "Default")
      (node (ref "SB24") (pin "1") (pinfunction "1_1") (pintype "passive"))
      (node (ref "VD52") (pin "2") (pinfunction "C_2") (pintype "passive"))
    )
    (net (code "127") (name "Net-(VD53-C)") (class "Default")
      (node (ref "SB25") (pin "1") (pinfunction "1_1") (pintype "passive"))
      (node (ref "VD53") (pin "2") (pinfunction "C_2") (pintype "passive"))
    )
    (net (code "128") (name "Net-(VD54-C)") (class "Default")
      (node (ref "SB26") (pin "1") (pinfunction "1_1") (pintype "passive"))
      (node (ref "VD54") (pin "2") (pinfunction "C_2") (pintype "passive"))
    )
    (net (code "129") (name "Net-(VD55-C)") (class "Default")
      (node (ref "SB27") (pin "1") (pinfunction "1_1") (pintype "passive"))
      (node (ref "VD55") (pin "2") (pinfunction "C_2") (pintype "passive"))
    )
    (net (code "130") (name "Net-(VD56-C)") (class "Default")
      (node (ref "SB28") (pin "1") (pinfunction "1_1") (pintype "passive"))
      (node (ref "VD56") (pin "2") (pinfunction "C_2") (pintype "passive"))
    )
    (net (code "131") (name "Net-(VD71-A)") (class "Default")
      (node (ref "R45") (pin "2") (pinfunction "2_2") (pintype "passive"))
      (node (ref "VD71") (pin "1") (pinfunction "A_1") (pintype "passive"))
      (node (ref "VD72") (pin "1") (pinfunction "A_1") (pintype "passive"))
      (node (ref "VD73") (pin "1") (pinfunction "A_1") (pintype "passive"))
      (node (ref "VD74") (pin "1") (pinfunction "A_1") (pintype "passive"))
      (node (ref "VD75") (pin "1") (pinfunction "A_1") (pintype "passive"))
      (node (ref "VD76") (pin "1") (pinfunction "A_1") (pintype "passive"))
      (node (ref "VD77") (pin "1") (pinfunction "A_1") (pintype "passive"))
      (node (ref "VD78") (pin "1") (pinfunction "A_1") (pintype "passive"))
      (node (ref "VD79") (pin "1") (pinfunction "A_1") (pintype "passive"))
      (node (ref "VD80") (pin "1") (pinfunction "A_1") (pintype "passive"))
      (node (ref "VD81") (pin "1") (pinfunction "A_1") (pintype "passive"))
      (node (ref "VD82") (pin "1") (pinfunction "A_1") (pintype "passive"))
      (node (ref "VD83") (pin "1") (pinfunction "A_1") (pintype "passive"))
      (node (ref "VD84") (pin "1") (pinfunction "A_1") (pintype "passive"))
      (node (ref "X2") (pin "3") (pinfunction "3_3") (pintype "passive"))
    )
    (net (code "132") (name "Net-(VD71-C)") (class "Default")
      (node (ref "SB29") (pin "1") (pinfunction "1_1") (pintype "passive"))
      (node (ref "VD71") (pin "2") (pinfunction "C_2") (pintype "passive"))
    )
    (net (code "133") (name "Net-(VD72-C)") (class "Default")
      (node (ref "SB30") (pin "1") (pinfunction "1_1") (pintype "passive"))
      (node (ref "VD72") (pin "2") (pinfunction "C_2") (pintype "passive"))
    )
    (net (code "134") (name "Net-(VD73-C)") (class "Default")
      (node (ref "SB31") (pin "1") (pinfunction "1_1") (pintype "passive"))
      (node (ref "VD73") (pin "2") (pinfunction "C_2") (pintype "passive"))
    )
    (net (code "135") (name "Net-(VD74-C)") (class "Default")
      (node (ref "SB32") (pin "1") (pinfunction "1_1") (pintype "passive"))
      (node (ref "VD74") (pin "2") (pinfunction "C_2") (pintype "passive"))
    )
    (net (code "136") (name "Net-(VD75-C)") (class "Default")
      (node (ref "SB33") (pin "1") (pinfunction "1_1") (pintype "passive"))
      (node (ref "VD75") (pin "2") (pinfunction "C_2") (pintype "passive"))
    )
    (net (code "137") (name "Net-(VD76-C)") (class "Default")
      (node (ref "SB34") (pin "1") (pinfunction "1_1") (pintype "passive"))
      (node (ref "VD76") (pin "2") (pinfunction "C_2") (pintype "passive"))
    )
    (net (code "138") (name "Net-(VD77-C)") (class "Default")
      (node (ref "SB35") (pin "1") (pinfunction "1_1") (pintype "passive"))
      (node (ref "VD77") (pin "2") (pinfunction "C_2") (pintype "passive"))
    )
    (net (code "139") (name "Net-(VD78-C)") (class "Default")
      (node (ref "SB36") (pin "1") (pinfunction "1_1") (pintype "passive"))
      (node (ref "VD78") (pin "2") (pinfunction "C_2") (pintype "passive"))
    )
    (net (code "140") (name "Net-(VD79-C)") (class "Default")
      (node (ref "SB37") (pin "1") (pinfunction "1_1") (pintype "passive"))
      (node (ref "VD79") (pin "2") (pinfunction "C_2") (pintype "passive"))
    )
    (net (code "141") (name "Net-(VD80-C)") (class "Default")
      (node (ref "SB38") (pin "1") (pinfunction "1_1") (pintype "passive"))
      (node (ref "VD80") (pin "2") (pinfunction "C_2") (pintype "passive"))
    )
    (net (code "142") (name "Net-(VD81-C)") (class "Default")
      (node (ref "SB39") (pin "1") (pinfunction "1_1") (pintype "passive"))
      (node (ref "VD81") (pin "2") (pinfunction "C_2") (pintype "passive"))
    )
    (net (code "143") (name "Net-(VD82-C)") (class "Default")
      (node (ref "SB40") (pin "1") (pinfunction "1_1") (pintype "passive"))
      (node (ref "VD82") (pin "2") (pinfunction "C_2") (pintype "passive"))
    )
    (net (code "144") (name "Net-(VD83-C)") (class "Default")
      (node (ref "SB41") (pin "1") (pinfunction "1_1") (pintype "passive"))
      (node (ref "VD83") (pin "2") (pinfunction "C_2") (pintype "passive"))
    )
    (net (code "145") (name "Net-(VD84-C)") (class "Default")
      (node (ref "SB42") (pin "1") (pinfunction "1_1") (pintype "passive"))
      (node (ref "VD84") (pin "2") (pinfunction "C_2") (pintype "passive"))
    )
    (net (code "146") (name "Net-(VD99-C)") (class "Default")
      (node (ref "SB43") (pin "1") (pinfunction "1_1") (pintype "passive"))
      (node (ref "VD99") (pin "2") (pinfunction "C_2") (pintype "passive"))
    )
    (net (code "147") (name "Net-(VD100-A)") (class "Default")
      (node (ref "R60") (pin "2") (pinfunction "2_2") (pintype "passive"))
      (node (ref "VD100") (pin "1") (pinfunction "A_1") (pintype "passive"))
      (node (ref "VD101") (pin "1") (pinfunction "A_1") (pintype "passive"))
      (node (ref "VD102") (pin "1") (pinfunction "A_1") (pintype "passive"))
      (node (ref "VD103") (pin "1") (pinfunction "A_1") (pintype "passive"))
      (node (ref "VD104") (pin "1") (pinfunction "A_1") (pintype "passive"))
      (node (ref "VD105") (pin "1") (pinfunction "A_1") (pintype "passive"))
      (node (ref "VD106") (pin "1") (pinfunction "A_1") (pintype "passive"))
      (node (ref "VD107") (pin "1") (pinfunction "A_1") (pintype "passive"))
      (node (ref "VD108") (pin "1") (pinfunction "A_1") (pintype "passive"))
      (node (ref "VD109") (pin "1") (pinfunction "A_1") (pintype "passive"))
      (node (ref "VD110") (pin "1") (pinfunction "A_1") (pintype "passive"))
      (node (ref "VD111") (pin "1") (pinfunction "A_1") (pintype "passive"))
      (node (ref "VD112") (pin "1") (pinfunction "A_1") (pintype "passive"))
      (node (ref "VD99") (pin "1") (pinfunction "A_1") (pintype "passive"))
      (node (ref "X2") (pin "4") (pinfunction "4_4") (pintype "passive"))
    )
    (net (code "148") (name "Net-(VD100-C)") (class "Default")
      (node (ref "SB44") (pin "1") (pinfunction "1_1") (pintype "passive"))
      (node (ref "VD100") (pin "2") (pinfunction "C_2") (pintype "passive"))
    )
    (net (code "149") (name "Net-(VD101-C)") (class "Default")
      (node (ref "SB45") (pin "1") (pinfunction "1_1") (pintype "passive"))
      (node (ref "VD101") (pin "2") (pinfunction "C_2") (pintype "passive"))
    )
    (net (code "150") (name "Net-(VD102-C)") (class "Default")
      (node (ref "SB46") (pin "1") (pinfunction "1_1") (pintype "passive"))
      (node (ref "VD102") (pin "2") (pinfunction "C_2") (pintype "passive"))
    )
    (net (code "151") (name "Net-(VD103-C)") (class "Default")
      (node (ref "SB47") (pin "1") (pinfunction "1_1") (pintype "passive"))
      (node (ref "VD103") (pin "2") (pinfunction "C_2") (pintype "passive"))
    )
    (net (code "152") (name "Net-(VD104-C)") (class "Default")
      (node (ref "SB48") (pin "1") (pinfunction "1_1") (pintype "passive"))
      (node (ref "VD104") (pin "2") (pinfunction "C_2") (pintype "passive"))
    )
    (net (code "153") (name "Net-(VD105-C)") (class "Default")
      (node (ref "SB49") (pin "1") (pinfunction "1_1") (pintype "passive"))
      (node (ref "VD105") (pin "2") (pinfunction "C_2") (pintype "passive"))
    )
    (net (code "154") (name "Net-(VD106-C)") (class "Default")
      (node (ref "SB50") (pin "1") (pinfunction "1_1") (pintype "passive"))
      (node (ref "VD106") (pin "2") (pinfunction "C_2") (pintype "passive"))
    )
    (net (code "155") (name "Net-(VD107-C)") (class "Default")
      (node (ref "SB51") (pin "1") (pinfunction "1_1") (pintype "passive"))
      (node (ref "VD107") (pin "2") (pinfunction "C_2") (pintype "passive"))
    )
    (net (code "156") (name "Net-(VD108-C)") (class "Default")
      (node (ref "SB52") (pin "1") (pinfunction "1_1") (pintype "passive"))
      (node (ref "VD108") (pin "2") (pinfunction "C_2") (pintype "passive"))
    )
    (net (code "157") (name "Net-(VD109-C)") (class "Default")
      (node (ref "SB53") (pin "1") (pinfunction "1_1") (pintype "passive"))
      (node (ref "VD109") (pin "2") (pinfunction "C_2") (pintype "passive"))
    )
    (net (code "158") (name "Net-(VD110-C)") (class "Default")
      (node (ref "SB54") (pin "1") (pinfunction "1_1") (pintype "passive"))
      (node (ref "VD110") (pin "2") (pinfunction "C_2") (pintype "passive"))
    )
    (net (code "159") (name "Net-(VD111-C)") (class "Default")
      (node (ref "SB55") (pin "1") (pinfunction "1_1") (pintype "passive"))
      (node (ref "VD111") (pin "2") (pinfunction "C_2") (pintype "passive"))
    )
    (net (code "160") (name "Net-(VD112-C)") (class "Default")
      (node (ref "SB56") (pin "1") (pinfunction "1_1") (pintype "passive"))
      (node (ref "VD112") (pin "2") (pinfunction "C_2") (pintype "passive"))
    )
    (net (code "161") (name "Net-(VD127-A)") (class "Default")
      (node (ref "R75") (pin "2") (pinfunction "2_2") (pintype "passive"))
      (node (ref "VD127") (pin "1") (pinfunction "A_1") (pintype "passive"))
      (node (ref "VD128") (pin "1") (pinfunction "A_1") (pintype "passive"))
      (node (ref "VD129") (pin "1") (pinfunction "A_1") (pintype "passive"))
      (node (ref "VD130") (pin "1") (pinfunction "A_1") (pintype "passive"))
      (node (ref "VD131") (pin "1") (pinfunction "A_1") (pintype "passive"))
      (node (ref "VD132") (pin "1") (pinfunction "A_1") (pintype "passive"))
      (node (ref "VD133") (pin "1") (pinfunction "A_1") (pintype "passive"))
      (node (ref "VD134") (pin "1") (pinfunction "A_1") (pintype "passive"))
      (node (ref "VD135") (pin "1") (pinfunction "A_1") (pintype "passive"))
      (node (ref "VD136") (pin "1") (pinfunction "A_1") (pintype "passive"))
      (node (ref "VD137") (pin "1") (pinfunction "A_1") (pintype "passive"))
      (node (ref "VD138") (pin "1") (pinfunction "A_1") (pintype "passive"))
      (node (ref "VD139") (pin "1") (pinfunction "A_1") (pintype "passive"))
      (node (ref "VD140") (pin "1") (pinfunction "A_1") (pintype "passive"))
      (node (ref "X2") (pin "5") (pinfunction "5_5") (pintype "passive"))
    )
    (net (code "162") (name "Net-(VD127-C)") (class "Default")
      (node (ref "SB57") (pin "1") (pinfunction "1_1") (pintype "passive"))
      (node (ref "VD127") (pin "2") (pinfunction "C_2") (pintype "passive"))
    )
    (net (code "163") (name "Net-(VD128-C)") (class "Default")
      (node (ref "SB58") (pin "1") (pinfunction "1_1") (pintype "passive"))
      (node (ref "VD128") (pin "2") (pinfunction "C_2") (pintype "passive"))
    )
    (net (code "164") (name "Net-(VD129-C)") (class "Default")
      (node (ref "SB59") (pin "1") (pinfunction "1_1") (pintype "passive"))
      (node (ref "VD129") (pin "2") (pinfunction "C_2") (pintype "passive"))
    )
    (net (code "165") (name "Net-(VD130-C)") (class "Default")
      (node (ref "SB60") (pin "1") (pinfunction "1_1") (pintype "passive"))
      (node (ref "VD130") (pin "2") (pinfunction "C_2") (pintype "passive"))
    )
    (net (code "166") (name "Net-(VD131-C)") (class "Default")
      (node (ref "SB61") (pin "1") (pinfunction "1_1") (pintype "passive"))
      (node (ref "VD131") (pin "2") (pinfunction "C_2") (pintype "passive"))
    )
    (net (code "167") (name "Net-(VD132-C)") (class "Default")
      (node (ref "SB62") (pin "1") (pinfunction "1_1") (pintype "passive"))
      (node (ref "VD132") (pin "2") (pinfunction "C_2") (pintype "passive"))
    )
    (net (code "168") (name "Net-(VD133-C)") (class "Default")
      (node (ref "SB63") (pin "1") (pinfunction "1_1") (pintype "passive"))
      (node (ref "VD133") (pin "2") (pinfunction "C_2") (pintype "passive"))
    )
    (net (code "169") (name "Net-(VD134-C)") (class "Default")
      (node (ref "SB64") (pin "1") (pinfunction "1_1") (pintype "passive"))
      (node (ref "VD134") (pin "2") (pinfunction "C_2") (pintype "passive"))
    )
    (net (code "170") (name "Net-(VD135-C)") (class "Default")
      (node (ref "SB65") (pin "1") (pinfunction "1_1") (pintype "passive"))
      (node (ref "VD135") (pin "2") (pinfunction "C_2") (pintype "passive"))
    )
    (net (code "171") (name "Net-(VD136-C)") (class "Default")
      (node (ref "SB66") (pin "1") (pinfunction "1_1") (pintype "passive"))
      (node (ref "VD136") (pin "2") (pinfunction "C_2") (pintype "passive"))
    )
    (net (code "172") (name "Net-(VD137-C)") (class "Default")
      (node (ref "SB67") (pin "1") (pinfunction "1_1") (pintype "passive"))
      (node (ref "VD137") (pin "2") (pinfunction "C_2") (pintype "passive"))
    )
    (net (code "173") (name "Net-(VD138-C)") (class "Default")
      (node (ref "SB68") (pin "1") (pinfunction "1_1") (pintype "passive"))
      (node (ref "VD138") (pin "2") (pinfunction "C_2") (pintype "passive"))
    )
    (net (code "174") (name "Net-(VD139-C)") (class "Default")
      (node (ref "SB69") (pin "1") (pinfunction "1_1") (pintype "passive"))
      (node (ref "VD139") (pin "2") (pinfunction "C_2") (pintype "passive"))
    )
    (net (code "175") (name "Net-(VD140-C)") (class "Default")
      (node (ref "SB70") (pin "1") (pinfunction "1_1") (pintype "passive"))
      (node (ref "VD140") (pin "2") (pinfunction "C_2") (pintype "passive"))
    )
    (net (code "176") (name "Net-(VD155-A)") (class "Default")
      (node (ref "R90") (pin "2") (pinfunction "2_2") (pintype "passive"))
      (node (ref "VD155") (pin "1") (pinfunction "A_1") (pintype "passive"))
      (node (ref "VD156") (pin "1") (pinfunction "A_1") (pintype "passive"))
      (node (ref "VD157") (pin "1") (pinfunction "A_1") (pintype "passive"))
      (node (ref "VD158") (pin "1") (pinfunction "A_1") (pintype "passive"))
      (node (ref "VD159") (pin "1") (pinfunction "A_1") (pintype "passive"))
      (node (ref "VD160") (pin "1") (pinfunction "A_1") (pintype "passive"))
      (node (ref "VD161") (pin "1") (pinfunction "A_1") (pintype "passive"))
      (node (ref "VD162") (pin "1") (pinfunction "A_1") (pintype "passive"))
      (node (ref "VD163") (pin "1") (pinfunction "A_1") (pintype "passive"))
      (node (ref "VD164") (pin "1") (pinfunction "A_1") (pintype "passive"))
      (node (ref "VD165") (pin "1") (pinfunction "A_1") (pintype "passive"))
      (node (ref "VD166") (pin "1") (pinfunction "A_1") (pintype "passive"))
      (node (ref "VD167") (pin "1") (pinfunction "A_1") (pintype "passive"))
      (node (ref "VD168") (pin "1") (pinfunction "A_1") (pintype "passive"))
      (node (ref "X2") (pin "6") (pinfunction "6_6") (pintype "passive"))
    )
    (net (code "177") (name "Net-(VD155-C)") (class "Default")
      (node (ref "SB71") (pin "1") (pinfunction "1_1") (pintype "passive"))
      (node (ref "VD155") (pin "2") (pinfunction "C_2") (pintype "passive"))
    )
    (net (code "178") (name "Net-(VD156-C)") (class "Default")
      (node (ref "SB72") (pin "1") (pinfunction "1_1") (pintype "passive"))
      (node (ref "VD156") (pin "2") (pinfunction "C_2") (pintype "passive"))
    )
    (net (code "179") (name "Net-(VD157-C)") (class "Default")
      (node (ref "SB73") (pin "1") (pinfunction "1_1") (pintype "passive"))
      (node (ref "VD157") (pin "2") (pinfunction "C_2") (pintype "passive"))
    )
    (net (code "180") (name "Net-(VD158-C)") (class "Default")
      (node (ref "SB74") (pin "1") (pinfunction "1_1") (pintype "passive"))
      (node (ref "VD158") (pin "2") (pinfunction "C_2") (pintype "passive"))
    )
    (net (code "181") (name "Net-(VD159-C)") (class "Default")
      (node (ref "SB75") (pin "1") (pinfunction "1_1") (pintype "passive"))
      (node (ref "VD159") (pin "2") (pinfunction "C_2") (pintype "passive"))
    )
    (net (code "182") (name "Net-(VD160-C)") (class "Default")
      (node (ref "SB76") (pin "1") (pinfunction "1_1") (pintype "passive"))
      (node (ref "VD160") (pin "2") (pinfunction "C_2") (pintype "passive"))
    )
    (net (code "183") (name "Net-(VD161-C)") (class "Default")
      (node (ref "SB77") (pin "1") (pinfunction "1_1") (pintype "passive"))
      (node (ref "VD161") (pin "2") (pinfunction "C_2") (pintype "passive"))
    )
    (net (code "184") (name "Net-(VD162-C)") (class "Default")
      (node (ref "SB78") (pin "1") (pinfunction "1_1") (pintype "passive"))
      (node (ref "VD162") (pin "2") (pinfunction "C_2") (pintype "passive"))
    )
    (net (code "185") (name "Net-(VD163-C)") (class "Default")
      (node (ref "SB79") (pin "1") (pinfunction "1_1") (pintype "passive"))
      (node (ref "VD163") (pin "2") (pinfunction "C_2") (pintype "passive"))
    )
    (net (code "186") (name "Net-(VD164-C)") (class "Default")
      (node (ref "SB80") (pin "1") (pinfunction "1_1") (pintype "passive"))
      (node (ref "VD164") (pin "2") (pinfunction "C_2") (pintype "passive"))
    )
    (net (code "187") (name "Net-(VD165-C)") (class "Default")
      (node (ref "SB81") (pin "1") (pinfunction "1_1") (pintype "passive"))
      (node (ref "VD165") (pin "2") (pinfunction "C_2") (pintype "passive"))
    )
    (net (code "188") (name "Net-(VD166-C)") (class "Default")
      (node (ref "SB82") (pin "1") (pinfunction "1_1") (pintype "passive"))
      (node (ref "VD166") (pin "2") (pinfunction "C_2") (pintype "passive"))
    )
    (net (code "189") (name "Net-(VD167-C)") (class "Default")
      (node (ref "SB83") (pin "1") (pinfunction "1_1") (pintype "passive"))
      (node (ref "VD167") (pin "2") (pinfunction "C_2") (pintype "passive"))
    )
    (net (code "190") (name "Net-(VD168-C)") (class "Default")
      (node (ref "SB84") (pin "1") (pinfunction "1_1") (pintype "passive"))
      (node (ref "VD168") (pin "2") (pinfunction "C_2") (pintype "passive"))
    )
  )
)
